# tsunami.net
KiCad netlist of a schematic drawn in EAGLE
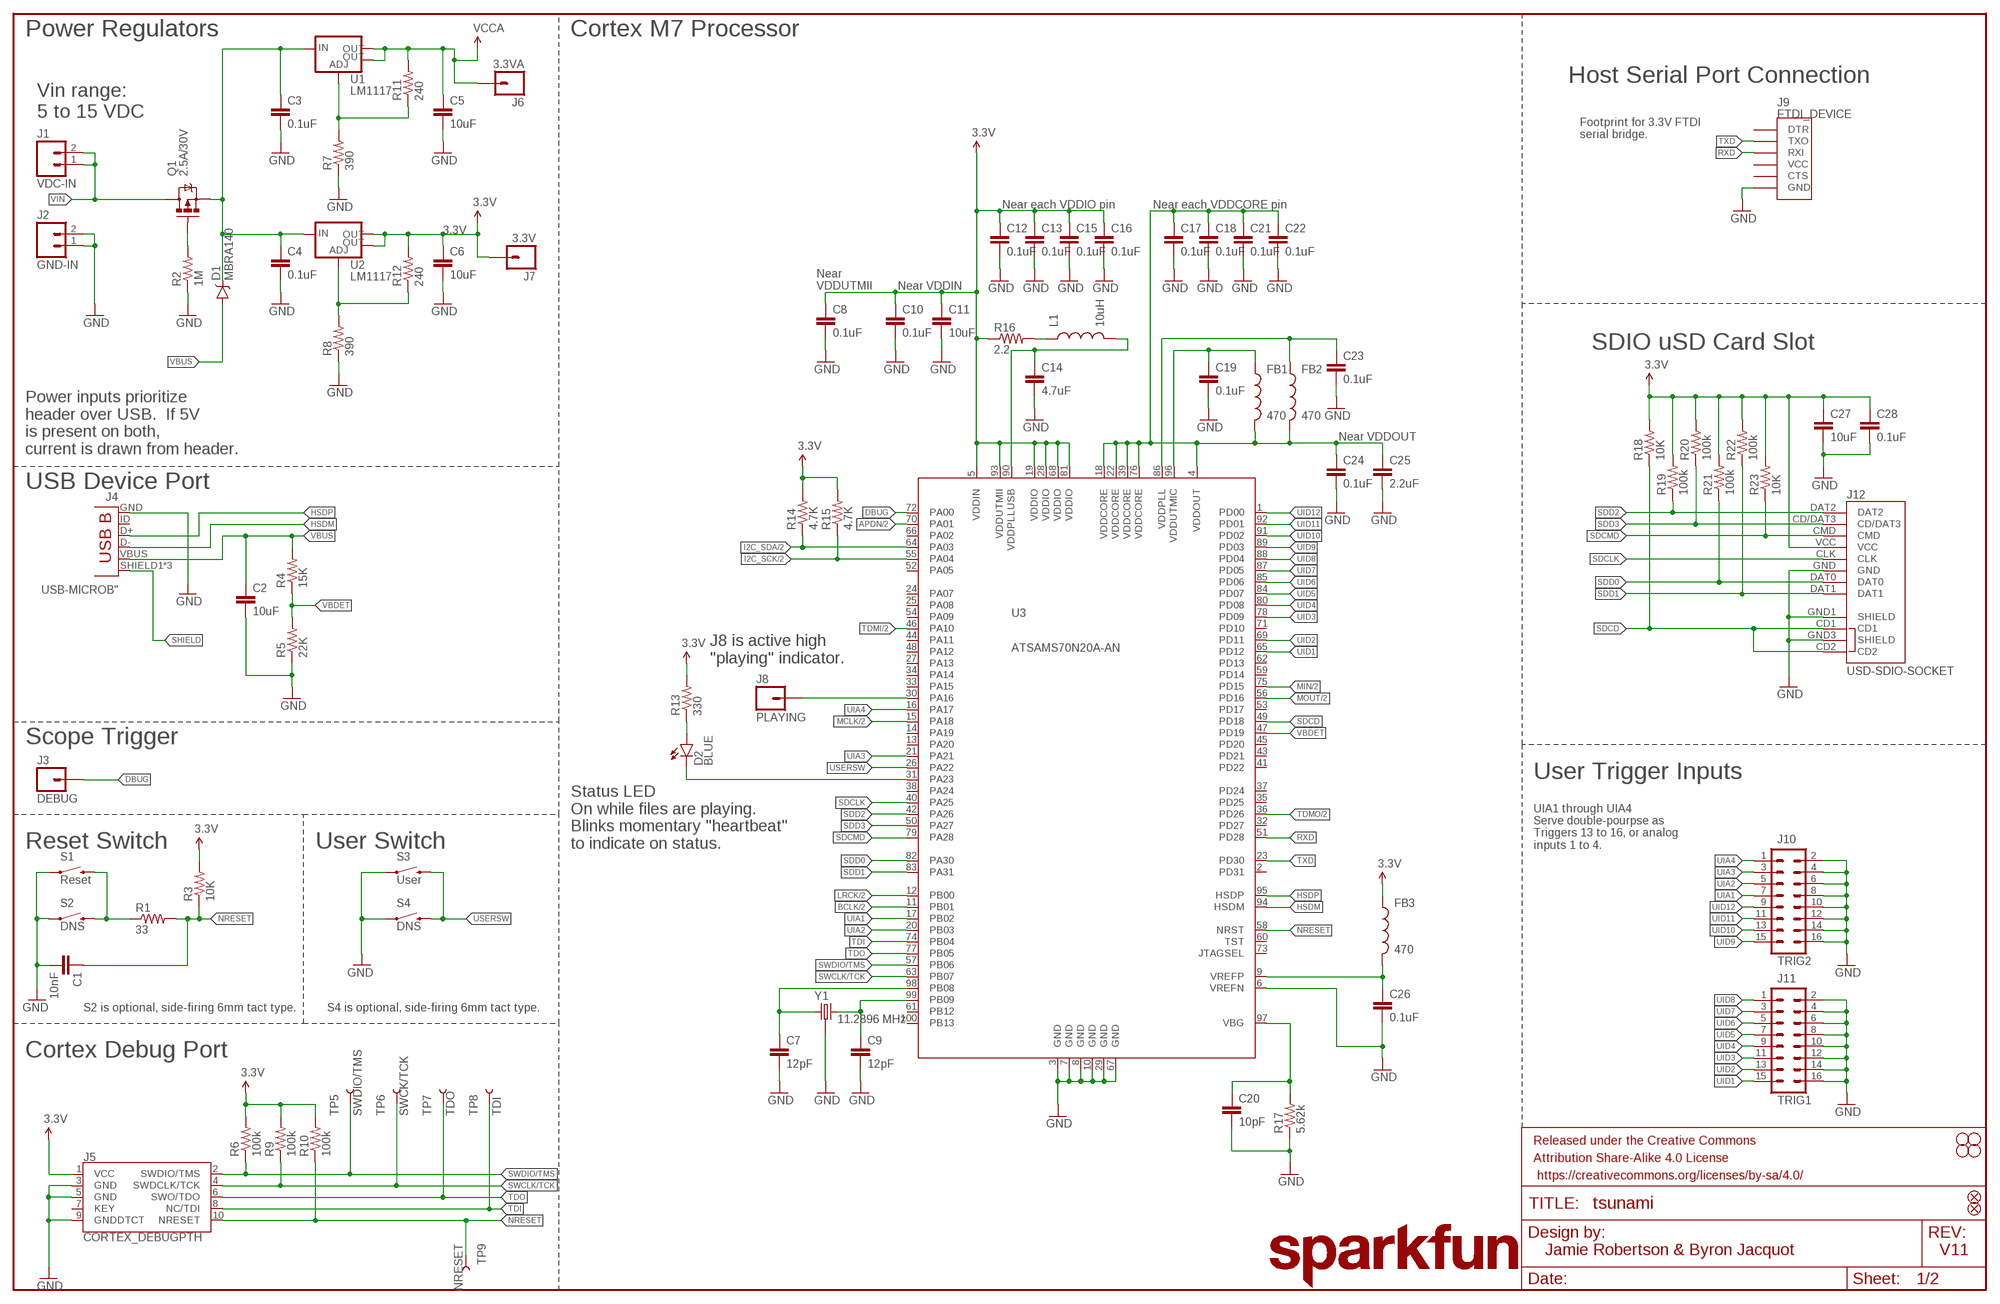
[diagram p0: schematic, sheet 1]
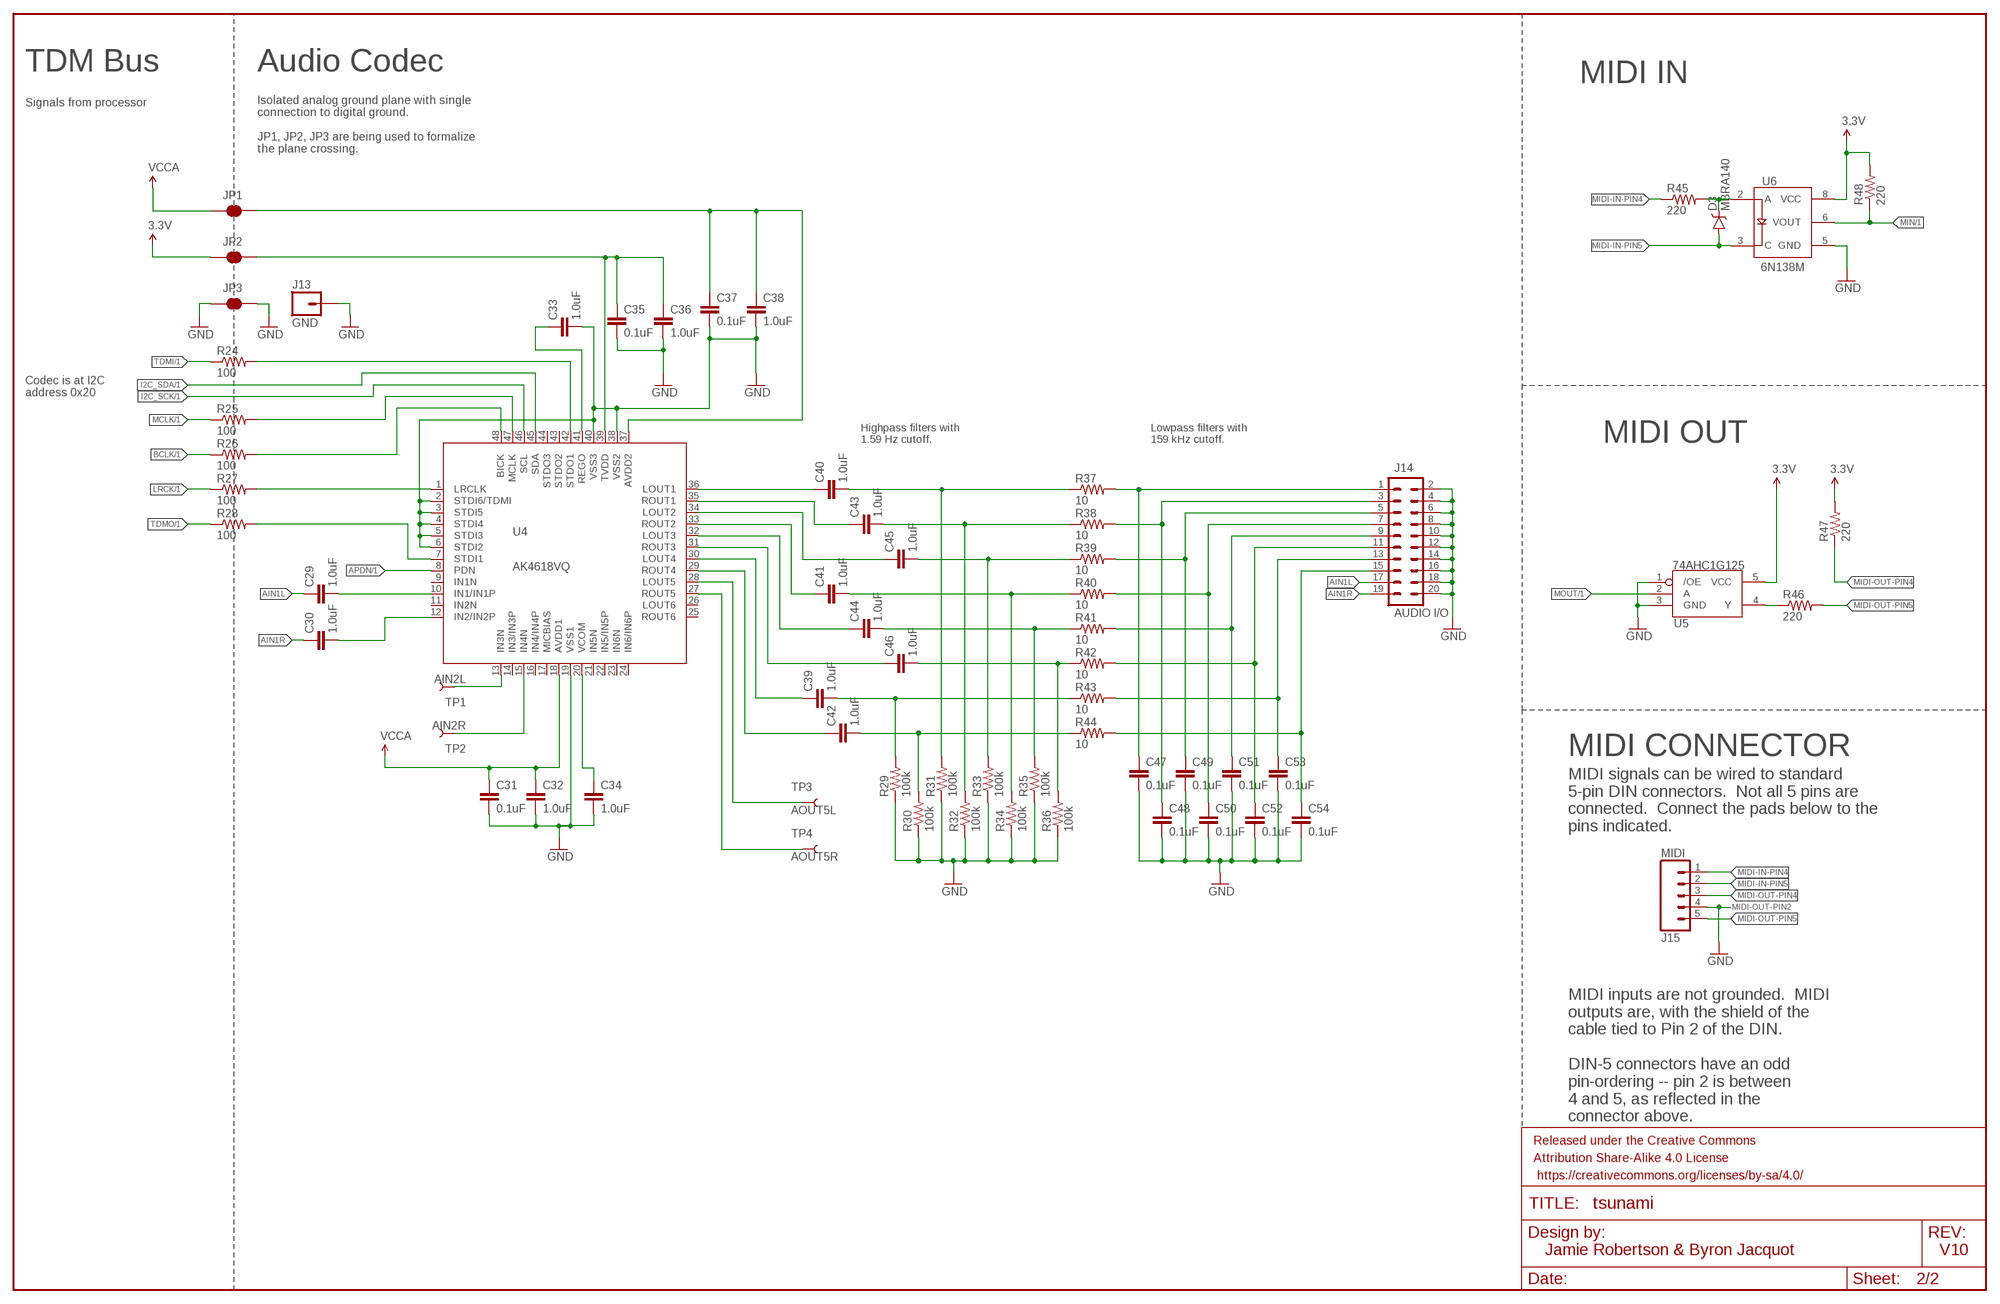
[diagram p1: schematic, sheet 2]

(export (version "E")
  (design (tool "Eeschema 10.0.6"))
  (components
    (comp (ref "C1")
      (value "10nF")
      (footprint "eagle-import:0603-CAP")
      (libsource (lib "eagle-import") (part "10NF/10000PF-50V-10%(0603)"))
    )
    (comp (ref "C2")
      (value "10uF")
      (footprint "eagle-import:0603-CAP")
      (libsource (lib "eagle-import") (part "10UF-6.3V-20%(0603)"))
    )
    (comp (ref "C3")
      (value "0.1uF")
      (footprint "eagle-import:0603-CAP")
      (libsource (lib "eagle-import") (part "0.1UF-25V(+80/-20%)(0603)"))
    )
    (comp (ref "C4")
      (value "0.1uF")
      (footprint "eagle-import:0603-CAP")
      (libsource (lib "eagle-import") (part "0.1UF-25V(+80/-20%)(0603)"))
    )
    (comp (ref "C5")
      (value "10uF")
      (footprint "eagle-import:0603-CAP")
      (libsource (lib "eagle-import") (part "10UF-6.3V-20%(0603)"))
    )
    (comp (ref "C6")
      (value "10uF")
      (footprint "eagle-import:0603-CAP")
      (libsource (lib "eagle-import") (part "10UF-6.3V-20%(0603)"))
    )
    (comp (ref "C7")
      (value "12pF")
      (footprint "eagle-import:0603-CAP")
      (libsource (lib "eagle-import") (part "12PF-50V-5%(0603)"))
    )
    (comp (ref "C8")
      (value "0.1uF")
      (footprint "eagle-import:0603-CAP")
      (libsource (lib "eagle-import") (part "0.1UF-25V(+80/-20%)(0603)"))
    )
    (comp (ref "C9")
      (value "12pF")
      (footprint "eagle-import:0603-CAP")
      (libsource (lib "eagle-import") (part "12PF-50V-5%(0603)"))
    )
    (comp (ref "C10")
      (value "0.1uF")
      (footprint "eagle-import:0603-CAP")
      (libsource (lib "eagle-import") (part "0.1UF-25V(+80/-20%)(0603)"))
    )
    (comp (ref "C11")
      (value "10uF")
      (footprint "eagle-import:0603-CAP")
      (libsource (lib "eagle-import") (part "10UF-6.3V-20%(0603)"))
    )
    (comp (ref "C12")
      (value "0.1uF")
      (footprint "eagle-import:0603-CAP")
      (libsource (lib "eagle-import") (part "0.1UF-25V(+80/-20%)(0603)"))
    )
    (comp (ref "C13")
      (value "0.1uF")
      (footprint "eagle-import:0603-CAP")
      (libsource (lib "eagle-import") (part "0.1UF-25V(+80/-20%)(0603)"))
    )
    (comp (ref "C14")
      (value "4.7uF")
      (footprint "eagle-import:0603-CAP")
      (libsource (lib "eagle-import") (part "4.7UF-6.3V-10%(0603)0603"))
    )
    (comp (ref "C15")
      (value "0.1uF")
      (footprint "eagle-import:0603-CAP")
      (libsource (lib "eagle-import") (part "0.1UF-25V(+80/-20%)(0603)"))
    )
    (comp (ref "C16")
      (value "0.1uF")
      (footprint "eagle-import:0603-CAP")
      (libsource (lib "eagle-import") (part "0.1UF-25V(+80/-20%)(0603)"))
    )
    (comp (ref "C17")
      (value "0.1uF")
      (footprint "eagle-import:0603-CAP")
      (libsource (lib "eagle-import") (part "0.1UF-25V(+80/-20%)(0603)"))
    )
    (comp (ref "C18")
      (value "0.1uF")
      (footprint "eagle-import:0603-CAP")
      (libsource (lib "eagle-import") (part "0.1UF-25V(+80/-20%)(0603)"))
    )
    (comp (ref "C19")
      (value "0.1uF")
      (footprint "eagle-import:0603-CAP")
      (libsource (lib "eagle-import") (part "0.1UF-25V(+80/-20%)(0603)"))
    )
    (comp (ref "C20")
      (value "10pF")
      (footprint "eagle-import:0603-CAP")
      (libsource (lib "eagle-import") (part "10PF-50V-5%(0603)"))
    )
    (comp (ref "C21")
      (value "0.1uF")
      (footprint "eagle-import:0603-CAP")
      (libsource (lib "eagle-import") (part "0.1UF-25V(+80/-20%)(0603)"))
    )
    (comp (ref "C22")
      (value "0.1uF")
      (footprint "eagle-import:0603-CAP")
      (libsource (lib "eagle-import") (part "0.1UF-25V(+80/-20%)(0603)"))
    )
    (comp (ref "C23")
      (value "0.1uF")
      (footprint "eagle-import:0603-CAP")
      (libsource (lib "eagle-import") (part "0.1UF-25V(+80/-20%)(0603)"))
    )
    (comp (ref "C24")
      (value "0.1uF")
      (footprint "eagle-import:0603-CAP")
      (libsource (lib "eagle-import") (part "0.1UF-25V(+80/-20%)(0603)"))
    )
    (comp (ref "C25")
      (value "2.2uF")
      (footprint "eagle-import:0603-CAP")
      (libsource (lib "eagle-import") (part "2.2UF-10V-20%(0603)"))
    )
    (comp (ref "C26")
      (value "0.1uF")
      (footprint "eagle-import:0603-CAP")
      (libsource (lib "eagle-import") (part "0.1UF-25V(+80/-20%)(0603)"))
    )
    (comp (ref "C27")
      (value "10uF")
      (footprint "eagle-import:0603-CAP")
      (libsource (lib "eagle-import") (part "10UF-6.3V-20%(0603)"))
    )
    (comp (ref "C28")
      (value "0.1uF")
      (footprint "eagle-import:0603-CAP")
      (libsource (lib "eagle-import") (part "0.1UF-25V(+80/-20%)(0603)"))
    )
    (comp (ref "D1")
      (value "MBRA140")
      (footprint "eagle-import:SMA-DIODE")
      (libsource (lib "eagle-import") (part "DIODE-SCHOTTKY-MBRA140"))
    )
    (comp (ref "D2")
      (value "BLUE")
      (footprint "eagle-import:LED-0603")
      (libsource (lib "eagle-import") (part "LED-BLUE0603"))
    )
    (comp (ref "FB1")
      (value "470")
      (footprint "eagle-import:0603")
      (libsource (lib "eagle-import") (part "INDUCTOR0603"))
    )
    (comp (ref "FB2")
      (value "470")
      (footprint "eagle-import:0603")
      (libsource (lib "eagle-import") (part "INDUCTOR0603"))
    )
    (comp (ref "FB3")
      (value "470")
      (footprint "eagle-import:0603")
      (libsource (lib "eagle-import") (part "INDUCTOR0603"))
    )
    (comp (ref "FD1")
      (value "FIDUCIALUFIDUCIAL")
      (footprint "eagle-import:MICRO-FIDUCIAL")
      (libsource (lib "eagle-import") (part "FIDUCIALUFIDUCIAL"))
    )
    (comp (ref "FD2")
      (value "FIDUCIALUFIDUCIAL")
      (footprint "eagle-import:MICRO-FIDUCIAL")
      (libsource (lib "eagle-import") (part "FIDUCIALUFIDUCIAL"))
    )
    (comp (ref "FRAME1")
      (value "FRAME-LEDGER")
      (footprint "eagle-import:CREATIVE_COMMONS")
      (libsource (lib "eagle-import") (part "FRAME-LEDGER"))
    )
    (comp (ref "H1")
      (value "STAND-OFF")
      (footprint "eagle-import:STAND-OFF")
      (libsource (lib "eagle-import") (part "STAND-OFF"))
    )
    (comp (ref "H2")
      (value "STAND-OFF")
      (footprint "eagle-import:STAND-OFF")
      (libsource (lib "eagle-import") (part "STAND-OFF"))
    )
    (comp (ref "H3")
      (value "STAND-OFF")
      (footprint "eagle-import:STAND-OFF")
      (libsource (lib "eagle-import") (part "STAND-OFF"))
    )
    (comp (ref "H4")
      (value "STAND-OFF")
      (footprint "eagle-import:STAND-OFF")
      (libsource (lib "eagle-import") (part "STAND-OFF"))
    )
    (comp (ref "J1")
      (value "VDC-IN")
      (footprint "eagle-import:1X02")
      (libsource (lib "eagle-import") (part "M02PTH"))
    )
    (comp (ref "J2")
      (value "GND-IN")
      (footprint "eagle-import:1X02")
      (libsource (lib "eagle-import") (part "M02PTH"))
    )
    (comp (ref "J3")
      (value "DEBUG")
      (footprint "eagle-import:1X01_NO_SILK")
      (libsource (lib "eagle-import") (part "M01PTH_NO_SILK_YES_STOP"))
    )
    (comp (ref "J4")
      (value "USB-MICROB\"")
      (footprint "eagle-import:USB-B-MICRO-SMD_V03")
      (libsource (lib "eagle-import") (part "USB-MICROB{dblquote}"))
    )
    (comp (ref "J5")
      (value "CORTEX_DEBUGPTH")
      (footprint "eagle-import:2X5-PTH-1.27MM")
      (libsource (lib "eagle-import") (part "CORTEX_DEBUGPTH"))
    )
    (comp (ref "J6")
      (value "3.3VA")
      (footprint "eagle-import:1X01_NO_SILK")
      (libsource (lib "eagle-import") (part "M01PTH_NO_SILK_YES_STOP"))
    )
    (comp (ref "J7")
      (value "3.3V")
      (footprint "eagle-import:1X01_NO_SILK")
      (libsource (lib "eagle-import") (part "M01PTH_NO_SILK_YES_STOP"))
    )
    (comp (ref "J8")
      (value "PLAYING")
      (footprint "eagle-import:1X01_NO_SILK")
      (libsource (lib "eagle-import") (part "M01PTH_NO_SILK_YES_STOP"))
    )
    (comp (ref "J9")
      (value "FTDI_DEVICE")
      (footprint "eagle-import:FTDI_DEVICE_SIDE")
      (libsource (lib "eagle-import") (part "FTDI_DEVICE"))
    )
    (comp (ref "J10")
      (value "TRIG2")
      (footprint "eagle-import:2X8")
      (libsource (lib "eagle-import") (part "M08X2"))
    )
    (comp (ref "J11")
      (value "TRIG1")
      (footprint "eagle-import:2X8")
      (libsource (lib "eagle-import") (part "M08X2"))
    )
    (comp (ref "J12")
      (value "USD-SDIO-SOCKET")
      (footprint "eagle-import:MICRO-SD-SOCKET-SDIO")
      (libsource (lib "eagle-import") (part "USD-SDIO-SOCKET"))
    )
    (comp (ref "L1")
      (value "10uH")
      (footprint "eagle-import:0805")
      (libsource (lib "eagle-import") (part "INDUCTOR0805"))
    )
    (comp (ref "LOGO1")
      (value "SFE_LOGO_NAME.2_INCH")
      (footprint "eagle-import:SFE_LOGO_NAME_.2")
      (libsource (lib "eagle-import") (part "SFE_LOGO_NAME.2_INCH"))
    )
    (comp (ref "Q1")
      (value "2.5A/30V")
      (footprint "eagle-import:SOT23-3")
      (libsource (lib "eagle-import") (part "MOSFET-PCHANNELDMG2307L"))
    )
    (comp (ref "R1")
      (value "33")
      (footprint "eagle-import:0603-RES")
      (libsource (lib "eagle-import") (part "33OHM1/10W1%(0603)"))
    )
    (comp (ref "R2")
      (value "1M")
      (footprint "eagle-import:0603-RES")
      (libsource (lib "eagle-import") (part "1MOHM-1/10W-1%(0603)"))
    )
    (comp (ref "R3")
      (value "10K")
      (footprint "eagle-import:0603-RES")
      (libsource (lib "eagle-import") (part "10KOHM-1/10W-1%(0603)0603"))
    )
    (comp (ref "R4")
      (value "15K")
      (footprint "eagle-import:0603-RES")
      (libsource (lib "eagle-import") (part "15KOHM1/10W1%(0603)0603"))
    )
    (comp (ref "R5")
      (value "22K")
      (footprint "eagle-import:0603-RES")
      (libsource (lib "eagle-import") (part "22KOHM1/10W1%(0603)"))
    )
    (comp (ref "R6")
      (value "100k")
      (footprint "eagle-import:0603-RES")
      (libsource (lib "eagle-import") (part "100KOHM-1/10W-1%(0603)"))
    )
    (comp (ref "R7")
      (value "390")
      (footprint "eagle-import:0603-RES")
      (libsource (lib "eagle-import") (part "390OHM1/10W1%(0603)"))
    )
    (comp (ref "R8")
      (value "390")
      (footprint "eagle-import:0603-RES")
      (libsource (lib "eagle-import") (part "390OHM1/10W1%(0603)"))
    )
    (comp (ref "R9")
      (value "100k")
      (footprint "eagle-import:0603-RES")
      (libsource (lib "eagle-import") (part "100KOHM-1/10W-1%(0603)"))
    )
    (comp (ref "R10")
      (value "100k")
      (footprint "eagle-import:0603-RES")
      (libsource (lib "eagle-import") (part "100KOHM-1/10W-1%(0603)"))
    )
    (comp (ref "R11")
      (value "240")
      (footprint "eagle-import:0603-RES")
      (libsource (lib "eagle-import") (part "240OHM1/10W1%(0603)"))
    )
    (comp (ref "R12")
      (value "240")
      (footprint "eagle-import:0603-RES")
      (libsource (lib "eagle-import") (part "240OHM1/10W1%(0603)"))
    )
    (comp (ref "R13")
      (value "330")
      (footprint "eagle-import:0603-RES")
      (libsource (lib "eagle-import") (part "330OHM1/10W1%(0603)"))
    )
    (comp (ref "R14")
      (value "4.7K")
      (footprint "eagle-import:0603-RES")
      (libsource (lib "eagle-import") (part "4.7KOHM-1/10W-1%(0603)"))
    )
    (comp (ref "R15")
      (value "4.7K")
      (footprint "eagle-import:0603-RES")
      (libsource (lib "eagle-import") (part "4.7KOHM-1/10W-1%(0603)"))
    )
    (comp (ref "R16")
      (value "2.2")
      (footprint "eagle-import:0603-RES")
      (libsource (lib "eagle-import") (part "2.2OHM-1/10W-5%(0603)"))
    )
    (comp (ref "R17")
      (value "5.62k")
      (footprint "eagle-import:0603-RES")
      (libsource (lib "eagle-import") (part "5.62KOHM1/10W1%(0603)"))
    )
    (comp (ref "R18")
      (value "10K")
      (footprint "eagle-import:0603-RES")
      (libsource (lib "eagle-import") (part "10KOHM-1/10W-1%(0603)0603"))
    )
    (comp (ref "R19")
      (value "100k")
      (footprint "eagle-import:0603-RES")
      (libsource (lib "eagle-import") (part "100KOHM-1/10W-1%(0603)"))
    )
    (comp (ref "R20")
      (value "100k")
      (footprint "eagle-import:0603-RES")
      (libsource (lib "eagle-import") (part "100KOHM-1/10W-1%(0603)"))
    )
    (comp (ref "R21")
      (value "100k")
      (footprint "eagle-import:0603-RES")
      (libsource (lib "eagle-import") (part "100KOHM-1/10W-1%(0603)"))
    )
    (comp (ref "R22")
      (value "100k")
      (footprint "eagle-import:0603-RES")
      (libsource (lib "eagle-import") (part "100KOHM-1/10W-1%(0603)"))
    )
    (comp (ref "R23")
      (value "10K")
      (footprint "eagle-import:0603-RES")
      (libsource (lib "eagle-import") (part "10KOHM-1/10W-1%(0603)0603"))
    )
    (comp (ref "S1")
      (value "Reset")
      (footprint "eagle-import:TACTILE-SWITCH-SMD")
      (libsource (lib "eagle-import") (part "SWITCH-MOMENTARY-2SMD"))
    )
    (comp (ref "S2")
      (value "DNS")
      (footprint "eagle-import:TACTILE-PTH-SIDEEZ")
      (libsource (lib "eagle-import") (part "SWITCH-MOMENTARY-2SIDE_EZ"))
    )
    (comp (ref "S3")
      (value "User")
      (footprint "eagle-import:TACTILE-SWITCH-SMD")
      (libsource (lib "eagle-import") (part "SWITCH-MOMENTARY-2SMD"))
    )
    (comp (ref "S4")
      (value "DNS")
      (footprint "eagle-import:TACTILE-PTH-SIDEEZ")
      (libsource (lib "eagle-import") (part "SWITCH-MOMENTARY-2SIDE_EZ"))
    )
    (comp (ref "TP5")
      (value "SWDIO/TMS")
      (footprint "eagle-import:TP_15TH")
      (libsource (lib "eagle-import") (part "TEST-POINTTP_15TH_THRU"))
    )
    (comp (ref "TP6")
      (value "SWCK/TCK")
      (footprint "eagle-import:TP_15TH")
      (libsource (lib "eagle-import") (part "TEST-POINTTP_15TH_THRU"))
    )
    (comp (ref "TP7")
      (value "TDO")
      (footprint "eagle-import:TP_15TH")
      (libsource (lib "eagle-import") (part "TEST-POINTTP_15TH_THRU"))
    )
    (comp (ref "TP8")
      (value "TDI")
      (footprint "eagle-import:TP_15TH")
      (libsource (lib "eagle-import") (part "TEST-POINTTP_15TH_THRU"))
    )
    (comp (ref "TP9")
      (value "NRESET")
      (footprint "eagle-import:TP_15TH")
      (libsource (lib "eagle-import") (part "TEST-POINTTP_15TH_THRU"))
    )
    (comp (ref "U1")
      (value "LM1117")
      (footprint "eagle-import:SOT223")
      (libsource (lib "eagle-import") (part "V_REG_LM1117SOT223"))
    )
    (comp (ref "U2")
      (value "LM1117")
      (footprint "eagle-import:SOT223")
      (libsource (lib "eagle-import") (part "V_REG_LM1117SOT223"))
    )
    (comp (ref "U3")
      (value "ATSAMS70N20A-AN")
      (footprint "eagle-import:LQFP100")
      (libsource (lib "eagle-import") (part "ATSAMS70NXXA-AN"))
    )
    (comp (ref "Y1")
      (value "11.2896 MHz")
      (footprint "eagle-import:CRYSTAL-OSC-SMD-5X3")
      (fields
        (field (name "DKPART") "887-2353-1-ND")
        (field (name "MFR") "txc")
        (field (name "MFRPART") "7B-11.2896MAAE-T")
      )
      (libsource (lib "eagle-import") (part "CRYSTAL-11.2896"))
    )
    (comp (ref "C29")
      (value "1.0uF")
      (footprint "eagle-import:0603-CAP")
      (libsource (lib "eagle-import") (part "1.0UF-16V-10%(0603)"))
    )
    (comp (ref "C30")
      (value "1.0uF")
      (footprint "eagle-import:0603-CAP")
      (libsource (lib "eagle-import") (part "1.0UF-16V-10%(0603)"))
    )
    (comp (ref "C31")
      (value "0.1uF")
      (footprint "eagle-import:0603-CAP")
      (libsource (lib "eagle-import") (part "0.1UF-25V(+80/-20%)(0603)"))
    )
    (comp (ref "C32")
      (value "1.0uF")
      (footprint "eagle-import:0603-CAP")
      (libsource (lib "eagle-import") (part "1.0UF-16V-10%(0603)"))
    )
    (comp (ref "C33")
      (value "1.0uF")
      (footprint "eagle-import:0603-CAP")
      (libsource (lib "eagle-import") (part "1.0UF-16V-10%(0603)"))
    )
    (comp (ref "C34")
      (value "1.0uF")
      (footprint "eagle-import:0603-CAP")
      (libsource (lib "eagle-import") (part "1.0UF-16V-10%(0603)"))
    )
    (comp (ref "C35")
      (value "0.1uF")
      (footprint "eagle-import:0603-CAP")
      (libsource (lib "eagle-import") (part "0.1UF-25V(+80/-20%)(0603)"))
    )
    (comp (ref "C36")
      (value "1.0uF")
      (footprint "eagle-import:0603-CAP")
      (libsource (lib "eagle-import") (part "1.0UF-16V-10%(0603)"))
    )
    (comp (ref "C37")
      (value "0.1uF")
      (footprint "eagle-import:0603-CAP")
      (libsource (lib "eagle-import") (part "0.1UF-25V(+80/-20%)(0603)"))
    )
    (comp (ref "C38")
      (value "1.0uF")
      (footprint "eagle-import:0603-CAP")
      (libsource (lib "eagle-import") (part "1.0UF-16V-10%(0603)"))
    )
    (comp (ref "C39")
      (value "1.0uF")
      (footprint "eagle-import:0603-CAP")
      (libsource (lib "eagle-import") (part "1.0UF-16V-10%(0603)"))
    )
    (comp (ref "C40")
      (value "1.0uF")
      (footprint "eagle-import:0603-CAP")
      (libsource (lib "eagle-import") (part "1.0UF-16V-10%(0603)"))
    )
    (comp (ref "C41")
      (value "1.0uF")
      (footprint "eagle-import:0603-CAP")
      (libsource (lib "eagle-import") (part "1.0UF-16V-10%(0603)"))
    )
    (comp (ref "C42")
      (value "1.0uF")
      (footprint "eagle-import:0603-CAP")
      (libsource (lib "eagle-import") (part "1.0UF-16V-10%(0603)"))
    )
    (comp (ref "C43")
      (value "1.0uF")
      (footprint "eagle-import:0603-CAP")
      (libsource (lib "eagle-import") (part "1.0UF-16V-10%(0603)"))
    )
    (comp (ref "C44")
      (value "1.0uF")
      (footprint "eagle-import:0603-CAP")
      (libsource (lib "eagle-import") (part "1.0UF-16V-10%(0603)"))
    )
    (comp (ref "C45")
      (value "1.0uF")
      (footprint "eagle-import:0603-CAP")
      (libsource (lib "eagle-import") (part "1.0UF-16V-10%(0603)"))
    )
    (comp (ref "C46")
      (value "1.0uF")
      (footprint "eagle-import:0603-CAP")
      (libsource (lib "eagle-import") (part "1.0UF-16V-10%(0603)"))
    )
    (comp (ref "C47")
      (value "0.1uF")
      (footprint "eagle-import:0603-CAP")
      (libsource (lib "eagle-import") (part "0.1UF-25V-5%(0603)"))
    )
    (comp (ref "C48")
      (value "0.1uF")
      (footprint "eagle-import:0603-CAP")
      (libsource (lib "eagle-import") (part "0.1UF-25V-5%(0603)"))
    )
    (comp (ref "C49")
      (value "0.1uF")
      (footprint "eagle-import:0603-CAP")
      (libsource (lib "eagle-import") (part "0.1UF-25V-5%(0603)"))
    )
    (comp (ref "C50")
      (value "0.1uF")
      (footprint "eagle-import:0603-CAP")
      (libsource (lib "eagle-import") (part "0.1UF-25V-5%(0603)"))
    )
    (comp (ref "C51")
      (value "0.1uF")
      (footprint "eagle-import:0603-CAP")
      (libsource (lib "eagle-import") (part "0.1UF-25V-5%(0603)"))
    )
    (comp (ref "C52")
      (value "0.1uF")
      (footprint "eagle-import:0603-CAP")
      (libsource (lib "eagle-import") (part "0.1UF-25V-5%(0603)"))
    )
    (comp (ref "C53")
      (value "0.1uF")
      (footprint "eagle-import:0603-CAP")
      (libsource (lib "eagle-import") (part "0.1UF-25V-5%(0603)"))
    )
    (comp (ref "C54")
      (value "0.1uF")
      (footprint "eagle-import:0603-CAP")
      (libsource (lib "eagle-import") (part "0.1UF-25V-5%(0603)"))
    )
    (comp (ref "D3")
      (value "MBRA140")
      (footprint "eagle-import:SMA-DIODE")
      (libsource (lib "eagle-import") (part "MBRA140"))
    )
    (comp (ref "FRAME2")
      (value "FRAME-LEDGER")
      (footprint "eagle-import:CREATIVE_COMMONS")
      (libsource (lib "eagle-import") (part "FRAME-LEDGER"))
    )
    (comp (ref "J13")
      (value "GND")
      (footprint "eagle-import:1X01_NO_SILK")
      (libsource (lib "eagle-import") (part "M01PTH_NO_SILK_YES_STOP"))
    )
    (comp (ref "J14")
      (value "AUDIO I/O")
      (footprint "eagle-import:2X10")
      (libsource (lib "eagle-import") (part "M10X2"))
    )
    (comp (ref "J15")
      (value "MIDI")
      (footprint "eagle-import:1X05_NO_SILK")
      (libsource (lib "eagle-import") (part "M05NO_SILK"))
    )
    (comp (ref "JP1")
      (value "JUMPER-PAD-2-NC_BY_TRACENO_SILK")
      (footprint "eagle-import:PAD-JUMPER-2-NC_BY_TRACE_NO_SILK")
      (libsource (lib "eagle-import") (part "JUMPER-PAD-2-NC_BY_TRACENO_SILK"))
    )
    (comp (ref "JP2")
      (value "JUMPER-PAD-2-NC_BY_TRACENO_SILK")
      (footprint "eagle-import:PAD-JUMPER-2-NC_BY_TRACE_NO_SILK")
      (libsource (lib "eagle-import") (part "JUMPER-PAD-2-NC_BY_TRACENO_SILK"))
    )
    (comp (ref "JP3")
      (value "JUMPER-PAD-2-NC_BY_TRACENO_SILK")
      (footprint "eagle-import:PAD-JUMPER-2-NC_BY_TRACE_NO_SILK")
      (libsource (lib "eagle-import") (part "JUMPER-PAD-2-NC_BY_TRACENO_SILK"))
    )
    (comp (ref "R24")
      (value "100")
      (footprint "eagle-import:0603-RES")
      (libsource (lib "eagle-import") (part "100OHM-1/10W-1%(0603)"))
    )
    (comp (ref "R25")
      (value "100")
      (footprint "eagle-import:0603-RES")
      (libsource (lib "eagle-import") (part "100OHM-1/10W-1%(0603)"))
    )
    (comp (ref "R26")
      (value "100")
      (footprint "eagle-import:0603-RES")
      (libsource (lib "eagle-import") (part "100OHM-1/10W-1%(0603)"))
    )
    (comp (ref "R27")
      (value "100")
      (footprint "eagle-import:0603-RES")
      (libsource (lib "eagle-import") (part "100OHM-1/10W-1%(0603)"))
    )
    (comp (ref "R28")
      (value "100")
      (footprint "eagle-import:0603-RES")
      (libsource (lib "eagle-import") (part "100OHM-1/10W-1%(0603)"))
    )
    (comp (ref "R29")
      (value "100k")
      (footprint "eagle-import:0603-RES")
      (libsource (lib "eagle-import") (part "100KOHM-1/10W-1%(0603)"))
    )
    (comp (ref "R30")
      (value "100k")
      (footprint "eagle-import:0603-RES")
      (libsource (lib "eagle-import") (part "100KOHM-1/10W-1%(0603)"))
    )
    (comp (ref "R31")
      (value "100k")
      (footprint "eagle-import:0603-RES")
      (libsource (lib "eagle-import") (part "100KOHM-1/10W-1%(0603)"))
    )
    (comp (ref "R32")
      (value "100k")
      (footprint "eagle-import:0603-RES")
      (libsource (lib "eagle-import") (part "100KOHM-1/10W-1%(0603)"))
    )
    (comp (ref "R33")
      (value "100k")
      (footprint "eagle-import:0603-RES")
      (libsource (lib "eagle-import") (part "100KOHM-1/10W-1%(0603)"))
    )
    (comp (ref "R34")
      (value "100k")
      (footprint "eagle-import:0603-RES")
      (libsource (lib "eagle-import") (part "100KOHM-1/10W-1%(0603)"))
    )
    (comp (ref "R35")
      (value "100k")
      (footprint "eagle-import:0603-RES")
      (libsource (lib "eagle-import") (part "100KOHM-1/10W-1%(0603)"))
    )
    (comp (ref "R36")
      (value "100k")
      (footprint "eagle-import:0603-RES")
      (libsource (lib "eagle-import") (part "100KOHM-1/10W-1%(0603)"))
    )
    (comp (ref "R37")
      (value "10")
      (footprint "eagle-import:0603-RES")
      (libsource (lib "eagle-import") (part "10OHM-1/10W-1%(0603)SMD"))
    )
    (comp (ref "R38")
      (value "10")
      (footprint "eagle-import:0603-RES")
      (libsource (lib "eagle-import") (part "10OHM-1/10W-1%(0603)SMD"))
    )
    (comp (ref "R39")
      (value "10")
      (footprint "eagle-import:0603-RES")
      (libsource (lib "eagle-import") (part "10OHM-1/10W-1%(0603)SMD"))
    )
    (comp (ref "R40")
      (value "10")
      (footprint "eagle-import:0603-RES")
      (libsource (lib "eagle-import") (part "10OHM-1/10W-1%(0603)SMD"))
    )
    (comp (ref "R41")
      (value "10")
      (footprint "eagle-import:0603-RES")
      (libsource (lib "eagle-import") (part "10OHM-1/10W-1%(0603)SMD"))
    )
    (comp (ref "R42")
      (value "10")
      (footprint "eagle-import:0603-RES")
      (libsource (lib "eagle-import") (part "10OHM-1/10W-1%(0603)SMD"))
    )
    (comp (ref "R43")
      (value "10")
      (footprint "eagle-import:0603-RES")
      (libsource (lib "eagle-import") (part "10OHM-1/10W-1%(0603)SMD"))
    )
    (comp (ref "R44")
      (value "10")
      (footprint "eagle-import:0603-RES")
      (libsource (lib "eagle-import") (part "10OHM-1/10W-1%(0603)SMD"))
    )
    (comp (ref "R45")
      (value "220")
      (footprint "eagle-import:0603-RES")
      (libsource (lib "eagle-import") (part "220OHM-1/10W-1%(0603)"))
    )
    (comp (ref "R46")
      (value "220")
      (footprint "eagle-import:0603-RES")
      (libsource (lib "eagle-import") (part "220OHM-1/10W-1%(0603)"))
    )
    (comp (ref "R47")
      (value "220")
      (footprint "eagle-import:0603-RES")
      (libsource (lib "eagle-import") (part "220OHM-1/10W-1%(0603)"))
    )
    (comp (ref "R48")
      (value "220")
      (footprint "eagle-import:0603-RES")
      (libsource (lib "eagle-import") (part "220OHM-1/10W-1%(0603)"))
    )
    (comp (ref "TP1")
      (value "AIN2L")
      (footprint "eagle-import:TP_15TH")
      (libsource (lib "eagle-import") (part "TEST-POINTTP_15TH_THRU"))
    )
    (comp (ref "TP2")
      (value "AIN2R")
      (footprint "eagle-import:TP_15TH")
      (libsource (lib "eagle-import") (part "TEST-POINTTP_15TH_THRU"))
    )
    (comp (ref "TP3")
      (value "AOUT5L")
      (footprint "eagle-import:TP_15TH")
      (libsource (lib "eagle-import") (part "TEST-POINTTP_15TH_THRU"))
    )
    (comp (ref "TP4")
      (value "AOUT5R")
      (footprint "eagle-import:TP_15TH")
      (libsource (lib "eagle-import") (part "TEST-POINTTP_15TH_THRU"))
    )
    (comp (ref "U4")
      (value "AK4618VQ")
      (footprint "eagle-import:LQFP-48")
      (libsource (lib "eagle-import") (part "AK4618VQSFE-PACKAGE"))
    )
    (comp (ref "U5")
      (value "74AHC1G125")
      (footprint "eagle-import:SOT23-5")
      (libsource (lib "eagle-import") (part "74AHC1G125"))
    )
    (comp (ref "U6")
      (value "6N138M")
      (footprint "eagle-import:8-SMD")
      (libsource (lib "eagle-import") (part "OPTO_DARL_6N138S"))
    )
  )
  (nets
    (net (code "1") (name "3.3V") (class "Default")
      (node (ref "C10") (pin "1") (pinfunction "1_1") (pintype "passive"))
      (node (ref "C11") (pin "1") (pinfunction "1_1") (pintype "passive"))
      (node (ref "C12") (pin "1") (pinfunction "1_1") (pintype "passive"))
      (node (ref "C13") (pin "1") (pinfunction "1_1") (pintype "passive"))
      (node (ref "C15") (pin "1") (pinfunction "1_1") (pintype "passive"))
      (node (ref "C16") (pin "1") (pinfunction "1_1") (pintype "passive"))
      (node (ref "C27") (pin "1") (pinfunction "1_1") (pintype "passive"))
      (node (ref "C28") (pin "1") (pinfunction "1_1") (pintype "passive"))
      (node (ref "C35") (pin "1") (pinfunction "1_1") (pintype "passive"))
      (node (ref "C36") (pin "1") (pinfunction "1_1") (pintype "passive"))
      (node (ref "C6") (pin "1") (pinfunction "1_1") (pintype "passive"))
      (node (ref "C8") (pin "1") (pinfunction "1_1") (pintype "passive"))
      (node (ref "FB3") (pin "1") (pinfunction "1_1") (pintype "passive"))
      (node (ref "J12") (pin "VCC") (pinfunction "VCC_VCC") (pintype "bidirectional"))
      (node (ref "J5") (pin "1") (pinfunction "VCC_1") (pintype "bidirectional"))
      (node (ref "J7") (pin "1") (pinfunction "1_1") (pintype "passive"))
      (node (ref "JP2") (pin "1") (pinfunction "1_1") (pintype "passive"))
      (node (ref "JP2") (pin "2") (pinfunction "2_2") (pintype "passive"))
      (node (ref "R10") (pin "2") (pinfunction "2_2") (pintype "passive"))
      (node (ref "R12") (pin "2") (pinfunction "2_2") (pintype "passive"))
      (node (ref "R13") (pin "2") (pinfunction "2_2") (pintype "passive"))
      (node (ref "R14") (pin "2") (pinfunction "2_2") (pintype "passive"))
      (node (ref "R15") (pin "2") (pinfunction "2_2") (pintype "passive"))
      (node (ref "R16") (pin "1") (pinfunction "1_1") (pintype "passive"))
      (node (ref "R18") (pin "2") (pinfunction "2_2") (pintype "passive"))
      (node (ref "R19") (pin "2") (pinfunction "2_2") (pintype "passive"))
      (node (ref "R20") (pin "2") (pinfunction "2_2") (pintype "passive"))
      (node (ref "R21") (pin "2") (pinfunction "2_2") (pintype "passive"))
      (node (ref "R22") (pin "2") (pinfunction "2_2") (pintype "passive"))
      (node (ref "R23") (pin "2") (pinfunction "2_2") (pintype "passive"))
      (node (ref "R3") (pin "2") (pinfunction "2_2") (pintype "passive"))
      (node (ref "R47") (pin "2") (pinfunction "2_2") (pintype "passive"))
      (node (ref "R48") (pin "2") (pinfunction "2_2") (pintype "passive"))
      (node (ref "R6") (pin "2") (pinfunction "2_2") (pintype "passive"))
      (node (ref "R9") (pin "2") (pinfunction "2_2") (pintype "passive"))
      (node (ref "U2") (pin "2") (pinfunction "OUT_2") (pintype "output"))
      (node (ref "U2") (pin "4") (pinfunction "OUT_4") (pintype "output"))
      (node (ref "U3") (pin "19") (pinfunction "VDDIO_19") (pintype "bidirectional"))
      (node (ref "U3") (pin "28") (pinfunction "VDDIO_28") (pintype "bidirectional"))
      (node (ref "U3") (pin "5") (pinfunction "VDDIN_5") (pintype "bidirectional"))
      (node (ref "U3") (pin "68") (pinfunction "VDDIO_68") (pintype "bidirectional"))
      (node (ref "U3") (pin "81") (pinfunction "VDDIO_81") (pintype "bidirectional"))
      (node (ref "U3") (pin "93") (pinfunction "VDDUTMII_93") (pintype "bidirectional"))
      (node (ref "U4") (pin "39") (pinfunction "TVDD_39") (pintype "bidirectional"))
      (node (ref "U5") (pin "5") (pinfunction "VCC_5") (pintype "bidirectional"))
      (node (ref "U6") (pin "8") (pinfunction "VCC_8") (pintype "bidirectional"))
    )
    (net (code "2") (name "AIN1L") (class "Default")
      (node (ref "C29") (pin "1") (pinfunction "1_1") (pintype "passive"))
      (node (ref "J14") (pin "17") (pinfunction "17_17") (pintype "passive"))
    )
    (net (code "3") (name "AIN1R") (class "Default")
      (node (ref "C30") (pin "1") (pinfunction "1_1") (pintype "passive"))
      (node (ref "J14") (pin "19") (pinfunction "19_19") (pintype "passive"))
    )
    (net (code "4") (name "APDN") (class "Default")
      (node (ref "U3") (pin "70") (pinfunction "PA01_70") (pintype "bidirectional"))
      (node (ref "U4") (pin "8") (pinfunction "PDN_8") (pintype "bidirectional"))
    )
    (net (code "5") (name "BCLK") (class "Default")
      (node (ref "R26") (pin "1") (pinfunction "1_1") (pintype "passive"))
      (node (ref "U3") (pin "11") (pinfunction "PB01_11") (pintype "bidirectional"))
    )
    (net (code "6") (name "DBUG") (class "Default")
      (node (ref "J3") (pin "1") (pinfunction "1_1") (pintype "passive"))
      (node (ref "U3") (pin "72") (pinfunction "PA00_72") (pintype "bidirectional"))
    )
    (net (code "7") (name "GND") (class "Default")
      (node (ref "C1") (pin "2") (pinfunction "2_2") (pintype "passive"))
      (node (ref "C10") (pin "2") (pinfunction "2_2") (pintype "passive"))
      (node (ref "C11") (pin "2") (pinfunction "2_2") (pintype "passive"))
      (node (ref "C12") (pin "2") (pinfunction "2_2") (pintype "passive"))
      (node (ref "C13") (pin "2") (pinfunction "2_2") (pintype "passive"))
      (node (ref "C14") (pin "2") (pinfunction "2_2") (pintype "passive"))
      (node (ref "C15") (pin "2") (pinfunction "2_2") (pintype "passive"))
      (node (ref "C16") (pin "2") (pinfunction "2_2") (pintype "passive"))
      (node (ref "C17") (pin "2") (pinfunction "2_2") (pintype "passive"))
      (node (ref "C18") (pin "2") (pinfunction "2_2") (pintype "passive"))
      (node (ref "C19") (pin "2") (pinfunction "2_2") (pintype "passive"))
      (node (ref "C2") (pin "2") (pinfunction "2_2") (pintype "passive"))
      (node (ref "C20") (pin "2") (pinfunction "2_2") (pintype "passive"))
      (node (ref "C21") (pin "2") (pinfunction "2_2") (pintype "passive"))
      (node (ref "C22") (pin "2") (pinfunction "2_2") (pintype "passive"))
      (node (ref "C23") (pin "2") (pinfunction "2_2") (pintype "passive"))
      (node (ref "C24") (pin "2") (pinfunction "2_2") (pintype "passive"))
      (node (ref "C25") (pin "2") (pinfunction "2_2") (pintype "passive"))
      (node (ref "C26") (pin "2") (pinfunction "2_2") (pintype "passive"))
      (node (ref "C27") (pin "2") (pinfunction "2_2") (pintype "passive"))
      (node (ref "C28") (pin "2") (pinfunction "2_2") (pintype "passive"))
      (node (ref "C3") (pin "2") (pinfunction "2_2") (pintype "passive"))
      (node (ref "C31") (pin "2") (pinfunction "2_2") (pintype "passive"))
      (node (ref "C32") (pin "2") (pinfunction "2_2") (pintype "passive"))
      (node (ref "C33") (pin "2") (pinfunction "2_2") (pintype "passive"))
      (node (ref "C34") (pin "2") (pinfunction "2_2") (pintype "passive"))
      (node (ref "C35") (pin "2") (pinfunction "2_2") (pintype "passive"))
      (node (ref "C36") (pin "2") (pinfunction "2_2") (pintype "passive"))
      (node (ref "C37") (pin "2") (pinfunction "2_2") (pintype "passive"))
      (node (ref "C38") (pin "2") (pinfunction "2_2") (pintype "passive"))
      (node (ref "C4") (pin "2") (pinfunction "2_2") (pintype "passive"))
      (node (ref "C47") (pin "2") (pinfunction "2_2") (pintype "passive"))
      (node (ref "C48") (pin "2") (pinfunction "2_2") (pintype "passive"))
      (node (ref "C49") (pin "2") (pinfunction "2_2") (pintype "passive"))
      (node (ref "C5") (pin "2") (pinfunction "2_2") (pintype "passive"))
      (node (ref "C50") (pin "2") (pinfunction "2_2") (pintype "passive"))
      (node (ref "C51") (pin "2") (pinfunction "2_2") (pintype "passive"))
      (node (ref "C52") (pin "2") (pinfunction "2_2") (pintype "passive"))
      (node (ref "C53") (pin "2") (pinfunction "2_2") (pintype "passive"))
      (node (ref "C54") (pin "2") (pinfunction "2_2") (pintype "passive"))
      (node (ref "C6") (pin "2") (pinfunction "2_2") (pintype "passive"))
      (node (ref "C7") (pin "2") (pinfunction "2_2") (pintype "passive"))
      (node (ref "C8") (pin "2") (pinfunction "2_2") (pintype "passive"))
      (node (ref "C9") (pin "2") (pinfunction "2_2") (pintype "passive"))
      (node (ref "J10") (pin "10") (pinfunction "10_10") (pintype "passive"))
      (node (ref "J10") (pin "12") (pinfunction "12_12") (pintype "passive"))
      (node (ref "J10") (pin "14") (pinfunction "14_14") (pintype "passive"))
      (node (ref "J10") (pin "16") (pinfunction "16_16") (pintype "passive"))
      (node (ref "J10") (pin "2") (pinfunction "2_2") (pintype "passive"))
      (node (ref "J10") (pin "4") (pinfunction "4_4") (pintype "passive"))
      (node (ref "J10") (pin "6") (pinfunction "6_6") (pintype "passive"))
      (node (ref "J10") (pin "8") (pinfunction "8_8") (pintype "passive"))
      (node (ref "J11") (pin "10") (pinfunction "10_10") (pintype "passive"))
      (node (ref "J11") (pin "12") (pinfunction "12_12") (pintype "passive"))
      (node (ref "J11") (pin "14") (pinfunction "14_14") (pintype "passive"))
      (node (ref "J11") (pin "16") (pinfunction "16_16") (pintype "passive"))
      (node (ref "J11") (pin "2") (pinfunction "2_2") (pintype "passive"))
      (node (ref "J11") (pin "4") (pinfunction "4_4") (pintype "passive"))
      (node (ref "J11") (pin "6") (pinfunction "6_6") (pintype "passive"))
      (node (ref "J11") (pin "8") (pinfunction "8_8") (pintype "passive"))
      (node (ref "J12") (pin "GND") (pinfunction "GND_GND") (pintype "bidirectional"))
      (node (ref "J12") (pin "GND1") (pinfunction "SHIELD_GND1") (pintype "bidirectional"))
      (node (ref "J12") (pin "GND3") (pinfunction "SHIELD_GND3") (pintype "bidirectional"))
      (node (ref "J13") (pin "1") (pinfunction "1_1") (pintype "passive"))
      (node (ref "J14") (pin "10") (pinfunction "10_10") (pintype "passive"))
      (node (ref "J14") (pin "12") (pinfunction "12_12") (pintype "passive"))
      (node (ref "J14") (pin "14") (pinfunction "14_14") (pintype "passive"))
      (node (ref "J14") (pin "16") (pinfunction "16_16") (pintype "passive"))
      (node (ref "J14") (pin "18") (pinfunction "18_18") (pintype "passive"))
      (node (ref "J14") (pin "2") (pinfunction "2_2") (pintype "passive"))
      (node (ref "J14") (pin "20") (pinfunction "20_20") (pintype "passive"))
      (node (ref "J14") (pin "4") (pinfunction "4_4") (pintype "passive"))
      (node (ref "J14") (pin "6") (pinfunction "6_6") (pintype "passive"))
      (node (ref "J14") (pin "8") (pinfunction "8_8") (pintype "passive"))
      (node (ref "J15") (pin "4") (pinfunction "4_4") (pintype "passive"))
      (node (ref "J2") (pin "1") (pinfunction "1_1") (pintype "passive"))
      (node (ref "J2") (pin "2") (pinfunction "2_2") (pintype "passive"))
      (node (ref "J4") (pin "GND") (pinfunction "GND_GND") (pintype "bidirectional"))
      (node (ref "J5") (pin "3") (pinfunction "GND_3") (pintype "bidirectional"))
      (node (ref "J5") (pin "5") (pinfunction "GND_5") (pintype "bidirectional"))
      (node (ref "J5") (pin "9") (pinfunction "GNDDTCT_9") (pintype "bidirectional"))
      (node (ref "J9") (pin "P$6") (pinfunction "GND_P$6") (pintype "bidirectional"))
      (node (ref "JP3") (pin "1") (pinfunction "1_1") (pintype "passive"))
      (node (ref "JP3") (pin "2") (pinfunction "2_2") (pintype "passive"))
      (node (ref "R17") (pin "1") (pinfunction "1_1") (pintype "passive"))
      (node (ref "R2") (pin "1") (pinfunction "1_1") (pintype "passive"))
      (node (ref "R29") (pin "1") (pinfunction "1_1") (pintype "passive"))
      (node (ref "R30") (pin "1") (pinfunction "1_1") (pintype "passive"))
      (node (ref "R31") (pin "1") (pinfunction "1_1") (pintype "passive"))
      (node (ref "R32") (pin "1") (pinfunction "1_1") (pintype "passive"))
      (node (ref "R33") (pin "1") (pinfunction "1_1") (pintype "passive"))
      (node (ref "R34") (pin "1") (pinfunction "1_1") (pintype "passive"))
      (node (ref "R35") (pin "1") (pinfunction "1_1") (pintype "passive"))
      (node (ref "R36") (pin "1") (pinfunction "1_1") (pintype "passive"))
      (node (ref "R5") (pin "1") (pinfunction "1_1") (pintype "passive"))
      (node (ref "R7") (pin "1") (pinfunction "1_1") (pintype "passive"))
      (node (ref "R8") (pin "1") (pinfunction "1_1") (pintype "passive"))
      (node (ref "S1") (pin "1") (pinfunction "1_1") (pintype "passive"))
      (node (ref "S2") (pin "1") (pinfunction "1_1") (pintype "passive"))
      (node (ref "S3") (pin "1") (pinfunction "1_1") (pintype "passive"))
      (node (ref "S4") (pin "1") (pinfunction "1_1") (pintype "passive"))
      (node (ref "U3") (pin "10") (pinfunction "GND_10") (pintype "bidirectional"))
      (node (ref "U3") (pin "29") (pinfunction "GND_29") (pintype "bidirectional"))
      (node (ref "U3") (pin "3") (pinfunction "GND_3") (pintype "bidirectional"))
      (node (ref "U3") (pin "6") (pinfunction "VREFN_6") (pintype "bidirectional"))
      (node (ref "U3") (pin "67") (pinfunction "GND_67") (pintype "bidirectional"))
      (node (ref "U3") (pin "7") (pinfunction "GND_7") (pintype "bidirectional"))
      (node (ref "U3") (pin "8") (pinfunction "GND_8") (pintype "bidirectional"))
      (node (ref "U4") (pin "19") (pinfunction "VSS1_19") (pintype "bidirectional"))
      (node (ref "U4") (pin "2") (pinfunction "STDI6/TDMI_2") (pintype "bidirectional"))
      (node (ref "U4") (pin "3") (pinfunction "STDI5_3") (pintype "bidirectional"))
      (node (ref "U4") (pin "38") (pinfunction "VSS2_38") (pintype "bidirectional"))
      (node (ref "U4") (pin "4") (pinfunction "STDI4_4") (pintype "bidirectional"))
      (node (ref "U4") (pin "40") (pinfunction "VSS3_40") (pintype "bidirectional"))
      (node (ref "U4") (pin "5") (pinfunction "STDI3_5") (pintype "bidirectional"))
      (node (ref "U4") (pin "6") (pinfunction "STDI2_6") (pintype "bidirectional"))
      (node (ref "U5") (pin "1") (pinfunction "/OE_1") (pintype "bidirectional"))
      (node (ref "U5") (pin "3") (pinfunction "GND_3") (pintype "bidirectional"))
      (node (ref "U6") (pin "5") (pinfunction "GND_5") (pintype "bidirectional"))
      (node (ref "Y1") (pin "2") (pinfunction "3_2") (pintype "passive"))
      (node (ref "Y1") (pin "4") (pinfunction "3_4") (pintype "passive"))
    )
    (net (code "8") (name "HSDM") (class "Default")
      (node (ref "J4") (pin "D-") (pinfunction "D-_D-") (pintype "bidirectional"))
      (node (ref "U3") (pin "94") (pinfunction "HSDM_94") (pintype "bidirectional"))
    )
    (net (code "9") (name "HSDP") (class "Default")
      (node (ref "J4") (pin "D+") (pinfunction "D+_D+") (pintype "bidirectional"))
      (node (ref "U3") (pin "95") (pinfunction "HSDP_95") (pintype "bidirectional"))
    )
    (net (code "10") (name "I2C_SCK") (class "Default")
      (node (ref "R15") (pin "1") (pinfunction "1_1") (pintype "passive"))
      (node (ref "U3") (pin "55") (pinfunction "PA04_55") (pintype "bidirectional"))
      (node (ref "U4") (pin "46") (pinfunction "SCL_46") (pintype "bidirectional"))
    )
    (net (code "11") (name "I2C_SDA") (class "Default")
      (node (ref "R14") (pin "1") (pinfunction "1_1") (pintype "passive"))
      (node (ref "U3") (pin "64") (pinfunction "PA03_64") (pintype "bidirectional"))
      (node (ref "U4") (pin "45") (pinfunction "SDA_45") (pintype "bidirectional"))
    )
    (net (code "12") (name "LRCK") (class "Default")
      (node (ref "R27") (pin "1") (pinfunction "1_1") (pintype "passive"))
      (node (ref "U3") (pin "12") (pinfunction "PB00_12") (pintype "bidirectional"))
    )
    (net (code "13") (name "MCLK") (class "Default")
      (node (ref "R25") (pin "1") (pinfunction "1_1") (pintype "passive"))
      (node (ref "U3") (pin "15") (pinfunction "PA18_15") (pintype "bidirectional"))
    )
    (net (code "14") (name "MIDI-IN-PIN4") (class "Default")
      (node (ref "J15") (pin "1") (pinfunction "1_1") (pintype "passive"))
      (node (ref "R45") (pin "1") (pinfunction "1_1") (pintype "passive"))
    )
    (net (code "15") (name "MIDI-IN-PIN5") (class "Default")
      (node (ref "D3") (pin "A") (pinfunction "A_A") (pintype "passive"))
      (node (ref "J15") (pin "2") (pinfunction "2_2") (pintype "passive"))
      (node (ref "U6") (pin "3") (pinfunction "C_3") (pintype "bidirectional"))
    )
    (net (code "16") (name "MIDI-OUT-PIN4") (class "Default")
      (node (ref "J15") (pin "3") (pinfunction "3_3") (pintype "passive"))
      (node (ref "R47") (pin "1") (pinfunction "1_1") (pintype "passive"))
    )
    (net (code "17") (name "MIDI-OUT-PIN5") (class "Default")
      (node (ref "J15") (pin "5") (pinfunction "5_5") (pintype "passive"))
      (node (ref "R46") (pin "2") (pinfunction "2_2") (pintype "passive"))
    )
    (net (code "18") (name "MIN") (class "Default")
      (node (ref "R48") (pin "1") (pinfunction "1_1") (pintype "passive"))
      (node (ref "U3") (pin "75") (pinfunction "PD15_75") (pintype "bidirectional"))
      (node (ref "U6") (pin "6") (pinfunction "VOUT_6") (pintype "bidirectional"))
    )
    (net (code "19") (name "MOUT") (class "Default")
      (node (ref "U3") (pin "56") (pinfunction "PD16_56") (pintype "bidirectional"))
      (node (ref "U5") (pin "2") (pinfunction "A_2") (pintype "bidirectional"))
    )
    (net (code "20") (name "NRESET") (class "Default")
      (node (ref "C1") (pin "1") (pinfunction "1_1") (pintype "passive"))
      (node (ref "J5") (pin "10") (pinfunction "NRESET_10") (pintype "bidirectional"))
      (node (ref "R1") (pin "2") (pinfunction "2_2") (pintype "passive"))
      (node (ref "R10") (pin "1") (pinfunction "1_1") (pintype "passive"))
      (node (ref "R3") (pin "1") (pinfunction "1_1") (pintype "passive"))
      (node (ref "TP9") (pin "P$1") (pinfunction "1_P$1") (pintype "bidirectional"))
      (node (ref "U3") (pin "58") (pinfunction "NRST_58") (pintype "bidirectional"))
    )
    (net (code "21") (name "Net-(C39-Pad2)") (class "Default")
      (node (ref "C39") (pin "2") (pinfunction "2_2") (pintype "passive"))
      (node (ref "R29") (pin "2") (pinfunction "2_2") (pintype "passive"))
      (node (ref "R43") (pin "1") (pinfunction "1_1") (pintype "passive"))
    )
    (net (code "22") (name "Net-(C40-Pad2)") (class "Default")
      (node (ref "C40") (pin "2") (pinfunction "2_2") (pintype "passive"))
      (node (ref "R31") (pin "2") (pinfunction "2_2") (pintype "passive"))
      (node (ref "R37") (pin "1") (pinfunction "1_1") (pintype "passive"))
    )
    (net (code "23") (name "Net-(C41-Pad2)") (class "Default")
      (node (ref "C41") (pin "2") (pinfunction "2_2") (pintype "passive"))
      (node (ref "R34") (pin "2") (pinfunction "2_2") (pintype "passive"))
      (node (ref "R40") (pin "1") (pinfunction "1_1") (pintype "passive"))
    )
    (net (code "24") (name "Net-(C42-Pad2)") (class "Default")
      (node (ref "C42") (pin "2") (pinfunction "2_2") (pintype "passive"))
      (node (ref "R30") (pin "2") (pinfunction "2_2") (pintype "passive"))
      (node (ref "R44") (pin "1") (pinfunction "1_1") (pintype "passive"))
    )
    (net (code "25") (name "Net-(C43-Pad2)") (class "Default")
      (node (ref "C43") (pin "2") (pinfunction "2_2") (pintype "passive"))
      (node (ref "R32") (pin "2") (pinfunction "2_2") (pintype "passive"))
      (node (ref "R38") (pin "1") (pinfunction "1_1") (pintype "passive"))
    )
    (net (code "26") (name "Net-(C44-Pad2)") (class "Default")
      (node (ref "C44") (pin "2") (pinfunction "2_2") (pintype "passive"))
      (node (ref "R35") (pin "2") (pinfunction "2_2") (pintype "passive"))
      (node (ref "R41") (pin "1") (pinfunction "1_1") (pintype "passive"))
    )
    (net (code "27") (name "Net-(C45-Pad2)") (class "Default")
      (node (ref "C45") (pin "2") (pinfunction "2_2") (pintype "passive"))
      (node (ref "R33") (pin "2") (pinfunction "2_2") (pintype "passive"))
      (node (ref "R39") (pin "1") (pinfunction "1_1") (pintype "passive"))
    )
    (net (code "28") (name "Net-(C46-Pad2)") (class "Default")
      (node (ref "C46") (pin "2") (pinfunction "2_2") (pintype "passive"))
      (node (ref "R36") (pin "2") (pinfunction "2_2") (pintype "passive"))
      (node (ref "R42") (pin "1") (pinfunction "1_1") (pintype "passive"))
    )
    (net (code "29") (name "Net-(C47-Pad1)") (class "Default")
      (node (ref "C47") (pin "1") (pinfunction "1_1") (pintype "passive"))
      (node (ref "J14") (pin "1") (pinfunction "1_1") (pintype "passive"))
      (node (ref "R37") (pin "2") (pinfunction "2_2") (pintype "passive"))
    )
    (net (code "30") (name "Net-(C48-Pad1)") (class "Default")
      (node (ref "C48") (pin "1") (pinfunction "1_1") (pintype "passive"))
      (node (ref "J14") (pin "3") (pinfunction "3_3") (pintype "passive"))
      (node (ref "R38") (pin "2") (pinfunction "2_2") (pintype "passive"))
    )
    (net (code "31") (name "Net-(C49-Pad1)") (class "Default")
      (node (ref "C49") (pin "1") (pinfunction "1_1") (pintype "passive"))
      (node (ref "J14") (pin "5") (pinfunction "5_5") (pintype "passive"))
      (node (ref "R39") (pin "2") (pinfunction "2_2") (pintype "passive"))
    )
    (net (code "32") (name "Net-(C50-Pad1)") (class "Default")
      (node (ref "C50") (pin "1") (pinfunction "1_1") (pintype "passive"))
      (node (ref "J14") (pin "7") (pinfunction "7_7") (pintype "passive"))
      (node (ref "R40") (pin "2") (pinfunction "2_2") (pintype "passive"))
    )
    (net (code "33") (name "Net-(C51-Pad1)") (class "Default")
      (node (ref "C51") (pin "1") (pinfunction "1_1") (pintype "passive"))
      (node (ref "J14") (pin "9") (pinfunction "9_9") (pintype "passive"))
      (node (ref "R41") (pin "2") (pinfunction "2_2") (pintype "passive"))
    )
    (net (code "34") (name "Net-(C52-Pad1)") (class "Default")
      (node (ref "C52") (pin "1") (pinfunction "1_1") (pintype "passive"))
      (node (ref "J14") (pin "11") (pinfunction "11_11") (pintype "passive"))
      (node (ref "R42") (pin "2") (pinfunction "2_2") (pintype "passive"))
    )
    (net (code "35") (name "Net-(C53-Pad1)") (class "Default")
      (node (ref "C53") (pin "1") (pinfunction "1_1") (pintype "passive"))
      (node (ref "J14") (pin "13") (pinfunction "13_13") (pintype "passive"))
      (node (ref "R43") (pin "2") (pinfunction "2_2") (pintype "passive"))
    )
    (net (code "36") (name "Net-(C54-Pad1)") (class "Default")
      (node (ref "C54") (pin "1") (pinfunction "1_1") (pintype "passive"))
      (node (ref "J14") (pin "15") (pinfunction "15_15") (pintype "passive"))
      (node (ref "R44") (pin "2") (pinfunction "2_2") (pintype "passive"))
    )
    (net (code "37") (name "Net-(D2-PadA)") (class "Default")
      (node (ref "D2") (pin "A") (pinfunction "A_A") (pintype "passive"))
      (node (ref "R13") (pin "1") (pinfunction "1_1") (pintype "passive"))
    )
    (net (code "38") (name "Net-(L1-Pad1)") (class "Default")
      (node (ref "L1") (pin "1") (pinfunction "1_1") (pintype "passive"))
      (node (ref "R16") (pin "2") (pinfunction "2_2") (pintype "passive"))
    )
    (net (code "39") (name "Net-(Q1-G)") (class "Default")
      (node (ref "Q1") (pin "1") (pinfunction "G_1") (pintype "passive"))
      (node (ref "R2") (pin "2") (pinfunction "2_2") (pintype "passive"))
    )
    (net (code "40") (name "Net-(Q1-S)") (class "Default")
      (node (ref "C3") (pin "1") (pinfunction "1_1") (pintype "passive"))
      (node (ref "C4") (pin "1") (pinfunction "1_1") (pintype "passive"))
      (node (ref "D1") (pin "C") (pinfunction "C_C") (pintype "passive"))
      (node (ref "Q1") (pin "2") (pinfunction "S_2") (pintype "passive"))
      (node (ref "U1") (pin "3") (pinfunction "IN_3") (pintype "input"))
      (node (ref "U2") (pin "3") (pinfunction "IN_3") (pintype "input"))
    )
    (net (code "41") (name "Net-(S1-2)") (class "Default")
      (node (ref "R1") (pin "1") (pinfunction "1_1") (pintype "passive"))
      (node (ref "S1") (pin "3") (pinfunction "2_3") (pintype "passive"))
      (node (ref "S2") (pin "2") (pinfunction "2_2") (pintype "passive"))
    )
    (net (code "42") (name "Net-(TP1-1)") (class "Default")
      (node (ref "TP1") (pin "P$1") (pinfunction "1_P$1") (pintype "bidirectional"))
      (node (ref "U4") (pin "13") (pinfunction "IN3N_13") (pintype "bidirectional"))
    )
    (net (code "43") (name "Net-(TP2-1)") (class "Default")
      (node (ref "TP2") (pin "P$1") (pinfunction "1_P$1") (pintype "bidirectional"))
      (node (ref "U4") (pin "15") (pinfunction "IN4N_15") (pintype "bidirectional"))
    )
    (net (code "44") (name "Net-(TP3-1)") (class "Default")
      (node (ref "TP3") (pin "P$1") (pinfunction "1_P$1") (pintype "bidirectional"))
      (node (ref "U4") (pin "28") (pinfunction "LOUT5_28") (pintype "bidirectional"))
    )
    (net (code "45") (name "Net-(TP4-1)") (class "Default")
      (node (ref "TP4") (pin "P$1") (pinfunction "1_P$1") (pintype "bidirectional"))
      (node (ref "U4") (pin "27") (pinfunction "ROUT5_27") (pintype "bidirectional"))
    )
    (net (code "46") (name "Net-(U1-ADJ)") (class "Default")
      (node (ref "R11") (pin "1") (pinfunction "1_1") (pintype "passive"))
      (node (ref "R7") (pin "2") (pinfunction "2_2") (pintype "passive"))
      (node (ref "U1") (pin "1") (pinfunction "ADJ_1") (pintype "input"))
    )
    (net (code "47") (name "Net-(U2-ADJ)") (class "Default")
      (node (ref "R12") (pin "1") (pinfunction "1_1") (pintype "passive"))
      (node (ref "R8") (pin "2") (pinfunction "2_2") (pintype "passive"))
      (node (ref "U2") (pin "1") (pinfunction "ADJ_1") (pintype "input"))
    )
    (net (code "48") (name "Net-(U3-PA16)") (class "Default")
      (node (ref "J8") (pin "1") (pinfunction "1_1") (pintype "passive"))
      (node (ref "U3") (pin "30") (pinfunction "PA16_30") (pintype "bidirectional"))
    )
    (net (code "49") (name "Net-(U3-PA23)") (class "Default")
      (node (ref "D2") (pin "C") (pinfunction "C_C") (pintype "passive"))
      (node (ref "U3") (pin "31") (pinfunction "PA23_31") (pintype "bidirectional"))
    )
    (net (code "50") (name "Net-(U3-PB08)") (class "Default")
      (node (ref "C7") (pin "1") (pinfunction "1_1") (pintype "passive"))
      (node (ref "U3") (pin "98") (pinfunction "PB08_98") (pintype "bidirectional"))
      (node (ref "Y1") (pin "1") (pinfunction "1_1") (pintype "passive"))
    )
    (net (code "51") (name "Net-(U3-PB09)") (class "Default")
      (node (ref "C9") (pin "1") (pinfunction "1_1") (pintype "passive"))
      (node (ref "U3") (pin "99") (pinfunction "PB09_99") (pintype "bidirectional"))
      (node (ref "Y1") (pin "3") (pinfunction "2_3") (pintype "passive"))
    )
    (net (code "52") (name "Net-(U3-VBG)") (class "Default")
      (node (ref "C20") (pin "1") (pinfunction "1_1") (pintype "passive"))
      (node (ref "R17") (pin "2") (pinfunction "2_2") (pintype "passive"))
      (node (ref "U3") (pin "97") (pinfunction "VBG_97") (pintype "bidirectional"))
    )
    (net (code "53") (name "Net-(U3-VDDOUT)") (class "Default")
      (node (ref "C17") (pin "1") (pinfunction "1_1") (pintype "passive"))
      (node (ref "C18") (pin "1") (pinfunction "1_1") (pintype "passive"))
      (node (ref "C21") (pin "1") (pinfunction "1_1") (pintype "passive"))
      (node (ref "C22") (pin "1") (pinfunction "1_1") (pintype "passive"))
      (node (ref "C24") (pin "1") (pinfunction "1_1") (pintype "passive"))
      (node (ref "C25") (pin "1") (pinfunction "1_1") (pintype "passive"))
      (node (ref "FB1") (pin "2") (pinfunction "2_2") (pintype "passive"))
      (node (ref "FB2") (pin "2") (pinfunction "2_2") (pintype "passive"))
      (node (ref "U3") (pin "18") (pinfunction "VDDCORE_18") (pintype "bidirectional"))
      (node (ref "U3") (pin "22") (pinfunction "VDDCORE_22") (pintype "bidirectional"))
      (node (ref "U3") (pin "39") (pinfunction "VDDCORE_39") (pintype "bidirectional"))
      (node (ref "U3") (pin "4") (pinfunction "VDDOUT_4") (pintype "bidirectional"))
      (node (ref "U3") (pin "76") (pinfunction "VDDCORE_76") (pintype "bidirectional"))
    )
    (net (code "54") (name "Net-(U3-VDDPLL)") (class "Default")
      (node (ref "C23") (pin "1") (pinfunction "1_1") (pintype "passive"))
      (node (ref "FB2") (pin "1") (pinfunction "1_1") (pintype "passive"))
      (node (ref "U3") (pin "86") (pinfunction "VDDPLL_86") (pintype "bidirectional"))
    )
    (net (code "55") (name "Net-(U3-VDDPLLUSB)") (class "Default")
      (node (ref "C14") (pin "1") (pinfunction "1_1") (pintype "passive"))
      (node (ref "L1") (pin "2") (pinfunction "2_2") (pintype "passive"))
      (node (ref "U3") (pin "90") (pinfunction "VDDPLLUSB_90") (pintype "bidirectional"))
    )
    (net (code "56") (name "Net-(U3-VDDUTMIC)") (class "Default")
      (node (ref "C19") (pin "1") (pinfunction "1_1") (pintype "passive"))
      (node (ref "FB1") (pin "1") (pinfunction "1_1") (pintype "passive"))
      (node (ref "U3") (pin "96") (pinfunction "VDDUTMIC_96") (pintype "bidirectional"))
    )
    (net (code "57") (name "Net-(U3-VREFP)") (class "Default")
      (node (ref "C26") (pin "1") (pinfunction "1_1") (pintype "passive"))
      (node (ref "FB3") (pin "2") (pinfunction "2_2") (pintype "passive"))
      (node (ref "U3") (pin "9") (pinfunction "VREFP_9") (pintype "bidirectional"))
    )
    (net (code "58") (name "Net-(U4-BICK)") (class "Default")
      (node (ref "R26") (pin "2") (pinfunction "2_2") (pintype "passive"))
      (node (ref "U4") (pin "48") (pinfunction "BICK_48") (pintype "bidirectional"))
    )
    (net (code "59") (name "Net-(U4-IN1{slash}IN1P)") (class "Default")
      (node (ref "C29") (pin "2") (pinfunction "2_2") (pintype "passive"))
      (node (ref "U4") (pin "10") (pinfunction "IN1/IN1P_10") (pintype "bidirectional"))
    )
    (net (code "60") (name "Net-(U4-IN2{slash}IN2P)") (class "Default")
      (node (ref "C30") (pin "2") (pinfunction "2_2") (pintype "passive"))
      (node (ref "U4") (pin "12") (pinfunction "IN2/IN2P_12") (pintype "bidirectional"))
    )
    (net (code "61") (name "Net-(U4-LOUT1)") (class "Default")
      (node (ref "C40") (pin "1") (pinfunction "1_1") (pintype "passive"))
      (node (ref "U4") (pin "36") (pinfunction "LOUT1_36") (pintype "bidirectional"))
    )
    (net (code "62") (name "Net-(U4-LOUT2)") (class "Default")
      (node (ref "C45") (pin "1") (pinfunction "1_1") (pintype "passive"))
      (node (ref "U4") (pin "34") (pinfunction "LOUT2_34") (pintype "bidirectional"))
    )
    (net (code "63") (name "Net-(U4-LOUT3)") (class "Default")
      (node (ref "C44") (pin "1") (pinfunction "1_1") (pintype "passive"))
      (node (ref "U4") (pin "32") (pinfunction "LOUT3_32") (pintype "bidirectional"))
    )
    (net (code "64") (name "Net-(U4-LOUT4)") (class "Default")
      (node (ref "C39") (pin "1") (pinfunction "1_1") (pintype "passive"))
      (node (ref "U4") (pin "30") (pinfunction "LOUT4_30") (pintype "bidirectional"))
    )
    (net (code "65") (name "Net-(U4-LRCLK)") (class "Default")
      (node (ref "R27") (pin "2") (pinfunction "2_2") (pintype "passive"))
      (node (ref "U4") (pin "1") (pinfunction "LRCLK_1") (pintype "bidirectional"))
    )
    (net (code "66") (name "Net-(U4-MCLK)") (class "Default")
      (node (ref "R25") (pin "2") (pinfunction "2_2") (pintype "passive"))
      (node (ref "U4") (pin "47") (pinfunction "MCLK_47") (pintype "bidirectional"))
    )
    (net (code "67") (name "Net-(U4-REGO)") (class "Default")
      (node (ref "C33") (pin "1") (pinfunction "1_1") (pintype "passive"))
      (node (ref "U4") (pin "41") (pinfunction "REGO_41") (pintype "bidirectional"))
    )
    (net (code "68") (name "Net-(U4-ROUT1)") (class "Default")
      (node (ref "C43") (pin "1") (pinfunction "1_1") (pintype "passive"))
      (node (ref "U4") (pin "35") (pinfunction "ROUT1_35") (pintype "bidirectional"))
    )
    (net (code "69") (name "Net-(U4-ROUT2)") (class "Default")
      (node (ref "C41") (pin "1") (pinfunction "1_1") (pintype "passive"))
      (node (ref "U4") (pin "33") (pinfunction "ROUT2_33") (pintype "bidirectional"))
    )
    (net (code "70") (name "Net-(U4-ROUT3)") (class "Default")
      (node (ref "C46") (pin "1") (pinfunction "1_1") (pintype "passive"))
      (node (ref "U4") (pin "31") (pinfunction "ROUT3_31") (pintype "bidirectional"))
    )
    (net (code "71") (name "Net-(U4-ROUT4)") (class "Default")
      (node (ref "C42") (pin "1") (pinfunction "1_1") (pintype "passive"))
      (node (ref "U4") (pin "29") (pinfunction "ROUT4_29") (pintype "bidirectional"))
    )
    (net (code "72") (name "Net-(U4-STDI1)") (class "Default")
      (node (ref "R28") (pin "2") (pinfunction "2_2") (pintype "passive"))
      (node (ref "U4") (pin "7") (pinfunction "STDI1_7") (pintype "bidirectional"))
    )
    (net (code "73") (name "Net-(U4-STDO1)") (class "Default")
      (node (ref "R24") (pin "2") (pinfunction "2_2") (pintype "passive"))
      (node (ref "U4") (pin "42") (pinfunction "STDO1_42") (pintype "bidirectional"))
    )
    (net (code "74") (name "Net-(U4-VCOM)") (class "Default")
      (node (ref "C34") (pin "1") (pinfunction "1_1") (pintype "passive"))
      (node (ref "U4") (pin "20") (pinfunction "VCOM_20") (pintype "bidirectional"))
    )
    (net (code "75") (name "Net-(U5-Y)") (class "Default")
      (node (ref "R46") (pin "1") (pinfunction "1_1") (pintype "passive"))
      (node (ref "U5") (pin "4") (pinfunction "Y_4") (pintype "bidirectional"))
    )
    (net (code "76") (name "Net-(U6-A)") (class "Default")
      (node (ref "D3") (pin "C") (pinfunction "C_C") (pintype "passive"))
      (node (ref "R45") (pin "2") (pinfunction "2_2") (pintype "passive"))
      (node (ref "U6") (pin "2") (pinfunction "A_2") (pintype "bidirectional"))
    )
    (net (code "77") (name "RXD") (class "Default")
      (node (ref "J9") (pin "P$3") (pinfunction "RXI_P$3") (pintype "bidirectional"))
      (node (ref "U3") (pin "51") (pinfunction "PD28_51") (pintype "bidirectional"))
    )
    (net (code "78") (name "SDCD") (class "Default")
      (node (ref "J12") (pin "CD1") (pinfunction "CD1_CD1") (pintype "bidirectional"))
      (node (ref "J12") (pin "CD2") (pinfunction "CD2_CD2") (pintype "bidirectional"))
      (node (ref "R18") (pin "1") (pinfunction "1_1") (pintype "passive"))
      (node (ref "U3") (pin "49") (pinfunction "PD18_49") (pintype "bidirectional"))
    )
    (net (code "79") (name "SDCLK") (class "Default")
      (node (ref "J12") (pin "CLK") (pinfunction "CLK_CLK") (pintype "bidirectional"))
      (node (ref "U3") (pin "40") (pinfunction "PA25_40") (pintype "bidirectional"))
    )
    (net (code "80") (name "SDCMD") (class "Default")
      (node (ref "J12") (pin "CMD") (pinfunction "CMD_CMD") (pintype "bidirectional"))
      (node (ref "R23") (pin "1") (pinfunction "1_1") (pintype "passive"))
      (node (ref "U3") (pin "79") (pinfunction "PA28_79") (pintype "bidirectional"))
    )
    (net (code "81") (name "SDD0") (class "Default")
      (node (ref "J12") (pin "DAT0") (pinfunction "DAT0_DAT0") (pintype "bidirectional"))
      (node (ref "R21") (pin "1") (pinfunction "1_1") (pintype "passive"))
      (node (ref "U3") (pin "82") (pinfunction "PA30_82") (pintype "bidirectional"))
    )
    (net (code "82") (name "SDD1") (class "Default")
      (node (ref "J12") (pin "DAT1") (pinfunction "DAT1_DAT1") (pintype "bidirectional"))
      (node (ref "R22") (pin "1") (pinfunction "1_1") (pintype "passive"))
      (node (ref "U3") (pin "83") (pinfunction "PA31_83") (pintype "bidirectional"))
    )
    (net (code "83") (name "SDD2") (class "Default")
      (node (ref "J12") (pin "DAT2") (pinfunction "DAT2_DAT2") (pintype "bidirectional"))
      (node (ref "R19") (pin "1") (pinfunction "1_1") (pintype "passive"))
      (node (ref "U3") (pin "42") (pinfunction "PA26_42") (pintype "bidirectional"))
    )
    (net (code "84") (name "SDD3") (class "Default")
      (node (ref "J12") (pin "CD/DAT3") (pinfunction "CD/DAT3_CD/DAT3") (pintype "bidirectional"))
      (node (ref "R20") (pin "1") (pinfunction "1_1") (pintype "passive"))
      (node (ref "U3") (pin "50") (pinfunction "PA27_50") (pintype "bidirectional"))
    )
    (net (code "85") (name "SHIELD") (class "Default")
      (node (ref "J4") (pin "SHIELD1") (pinfunction "SHIELD_SHIELD1") (pintype "bidirectional"))
      (node (ref "J4") (pin "SHIELD2") (pinfunction "SHIELD_SHIELD2") (pintype "bidirectional"))
      (node (ref "J4") (pin "SHIELD3") (pinfunction "SHIELD_SHIELD3") (pintype "bidirectional"))
    )
    (net (code "86") (name "SWCLK{slash}TCK") (class "Default")
      (node (ref "J5") (pin "4") (pinfunction "SWDCLK/TCK_4") (pintype "bidirectional"))
      (node (ref "R9") (pin "1") (pinfunction "1_1") (pintype "passive"))
      (node (ref "TP6") (pin "P$1") (pinfunction "1_P$1") (pintype "bidirectional"))
      (node (ref "U3") (pin "63") (pinfunction "PB07_63") (pintype "bidirectional"))
    )
    (net (code "87") (name "SWDIO{slash}TMS") (class "Default")
      (node (ref "J5") (pin "2") (pinfunction "SWDIO/TMS_2") (pintype "bidirectional"))
      (node (ref "R6") (pin "1") (pinfunction "1_1") (pintype "passive"))
      (node (ref "TP5") (pin "P$1") (pinfunction "1_P$1") (pintype "bidirectional"))
      (node (ref "U3") (pin "57") (pinfunction "PB06_57") (pintype "bidirectional"))
    )
    (net (code "88") (name "TDI") (class "Default")
      (node (ref "J5") (pin "8") (pinfunction "NC/TDI_8") (pintype "bidirectional"))
      (node (ref "TP8") (pin "P$1") (pinfunction "1_P$1") (pintype "bidirectional"))
      (node (ref "U3") (pin "74") (pinfunction "PB04_74") (pintype "bidirectional"))
    )
    (net (code "89") (name "TDMI") (class "Default")
      (node (ref "R24") (pin "1") (pinfunction "1_1") (pintype "passive"))
      (node (ref "U3") (pin "46") (pinfunction "PA10_46") (pintype "bidirectional"))
    )
    (net (code "90") (name "TDMO") (class "Default")
      (node (ref "R28") (pin "1") (pinfunction "1_1") (pintype "passive"))
      (node (ref "U3") (pin "36") (pinfunction "PD26_36") (pintype "bidirectional"))
    )
    (net (code "91") (name "TDO") (class "Default")
      (node (ref "J5") (pin "6") (pinfunction "SWO/TDO_6") (pintype "bidirectional"))
      (node (ref "TP7") (pin "P$1") (pinfunction "1_P$1") (pintype "bidirectional"))
      (node (ref "U3") (pin "77") (pinfunction "PB05_77") (pintype "bidirectional"))
    )
    (net (code "92") (name "TXD") (class "Default")
      (node (ref "J9") (pin "P$2") (pinfunction "TXO_P$2") (pintype "bidirectional"))
      (node (ref "U3") (pin "23") (pinfunction "PD30_23") (pintype "bidirectional"))
    )
    (net (code "93") (name "UIA1") (class "Default")
      (node (ref "J10") (pin "7") (pinfunction "7_7") (pintype "passive"))
      (node (ref "U3") (pin "17") (pinfunction "PB02_17") (pintype "bidirectional"))
    )
    (net (code "94") (name "UIA2") (class "Default")
      (node (ref "J10") (pin "5") (pinfunction "5_5") (pintype "passive"))
      (node (ref "U3") (pin "20") (pinfunction "PB03_20") (pintype "bidirectional"))
    )
    (net (code "95") (name "UIA3") (class "Default")
      (node (ref "J10") (pin "3") (pinfunction "3_3") (pintype "passive"))
      (node (ref "U3") (pin "21") (pinfunction "PA21_21") (pintype "bidirectional"))
    )
    (net (code "96") (name "UIA4") (class "Default")
      (node (ref "J10") (pin "1") (pinfunction "1_1") (pintype "passive"))
      (node (ref "U3") (pin "16") (pinfunction "PA17_16") (pintype "bidirectional"))
    )
    (net (code "97") (name "UID1") (class "Default")
      (node (ref "J11") (pin "15") (pinfunction "15_15") (pintype "passive"))
      (node (ref "U3") (pin "65") (pinfunction "PD12_65") (pintype "bidirectional"))
    )
    (net (code "98") (name "UID2") (class "Default")
      (node (ref "J11") (pin "13") (pinfunction "13_13") (pintype "passive"))
      (node (ref "U3") (pin "69") (pinfunction "PD11_69") (pintype "bidirectional"))
    )
    (net (code "99") (name "UID3") (class "Default")
      (node (ref "J11") (pin "11") (pinfunction "11_11") (pintype "passive"))
      (node (ref "U3") (pin "78") (pinfunction "PD09_78") (pintype "bidirectional"))
    )
    (net (code "100") (name "UID4") (class "Default")
      (node (ref "J11") (pin "9") (pinfunction "9_9") (pintype "passive"))
      (node (ref "U3") (pin "80") (pinfunction "PD08_80") (pintype "bidirectional"))
    )
    (net (code "101") (name "UID5") (class "Default")
      (node (ref "J11") (pin "7") (pinfunction "7_7") (pintype "passive"))
      (node (ref "U3") (pin "84") (pinfunction "PD07_84") (pintype "bidirectional"))
    )
    (net (code "102") (name "UID6") (class "Default")
      (node (ref "J11") (pin "5") (pinfunction "5_5") (pintype "passive"))
      (node (ref "U3") (pin "85") (pinfunction "PD06_85") (pintype "bidirectional"))
    )
    (net (code "103") (name "UID7") (class "Default")
      (node (ref "J11") (pin "3") (pinfunction "3_3") (pintype "passive"))
      (node (ref "U3") (pin "87") (pinfunction "PD05_87") (pintype "bidirectional"))
    )
    (net (code "104") (name "UID8") (class "Default")
      (node (ref "J11") (pin "1") (pinfunction "1_1") (pintype "passive"))
      (node (ref "U3") (pin "88") (pinfunction "PD04_88") (pintype "bidirectional"))
    )
    (net (code "105") (name "UID9") (class "Default")
      (node (ref "J10") (pin "15") (pinfunction "15_15") (pintype "passive"))
      (node (ref "U3") (pin "89") (pinfunction "PD03_89") (pintype "bidirectional"))
    )
    (net (code "106") (name "UID10") (class "Default")
      (node (ref "J10") (pin "13") (pinfunction "13_13") (pintype "passive"))
      (node (ref "U3") (pin "91") (pinfunction "PD02_91") (pintype "bidirectional"))
    )
    (net (code "107") (name "UID11") (class "Default")
      (node (ref "J10") (pin "11") (pinfunction "11_11") (pintype "passive"))
      (node (ref "U3") (pin "92") (pinfunction "PD01_92") (pintype "bidirectional"))
    )
    (net (code "108") (name "UID12") (class "Default")
      (node (ref "J10") (pin "9") (pinfunction "9_9") (pintype "passive"))
      (node (ref "U3") (pin "1") (pinfunction "PD00_1") (pintype "bidirectional"))
    )
    (net (code "109") (name "USERSW") (class "Default")
      (node (ref "S3") (pin "3") (pinfunction "2_3") (pintype "passive"))
      (node (ref "S4") (pin "2") (pinfunction "2_2") (pintype "passive"))
      (node (ref "U3") (pin "26") (pinfunction "PA22_26") (pintype "bidirectional"))
    )
    (net (code "110") (name "VBDET") (class "Default")
      (node (ref "R4") (pin "1") (pinfunction "1_1") (pintype "passive"))
      (node (ref "R5") (pin "2") (pinfunction "2_2") (pintype "passive"))
      (node (ref "U3") (pin "47") (pinfunction "PD19_47") (pintype "bidirectional"))
    )
    (net (code "111") (name "VBUS") (class "Default")
      (node (ref "C2") (pin "1") (pinfunction "1_1") (pintype "passive"))
      (node (ref "D1") (pin "A") (pinfunction "A_A") (pintype "passive"))
      (node (ref "J4") (pin "VBUS") (pinfunction "VBUS_VBUS") (pintype "bidirectional"))
      (node (ref "R4") (pin "2") (pinfunction "2_2") (pintype "passive"))
    )
    (net (code "112") (name "VCCA") (class "Default")
      (node (ref "C31") (pin "1") (pinfunction "1_1") (pintype "passive"))
      (node (ref "C32") (pin "1") (pinfunction "1_1") (pintype "passive"))
      (node (ref "C37") (pin "1") (pinfunction "1_1") (pintype "passive"))
      (node (ref "C38") (pin "1") (pinfunction "1_1") (pintype "passive"))
      (node (ref "C5") (pin "1") (pinfunction "1_1") (pintype "passive"))
      (node (ref "J6") (pin "1") (pinfunction "1_1") (pintype "passive"))
      (node (ref "JP1") (pin "1") (pinfunction "1_1") (pintype "passive"))
      (node (ref "JP1") (pin "2") (pinfunction "2_2") (pintype "passive"))
      (node (ref "R11") (pin "2") (pinfunction "2_2") (pintype "passive"))
      (node (ref "U1") (pin "2") (pinfunction "OUT_2") (pintype "output"))
      (node (ref "U1") (pin "4") (pinfunction "OUT_4") (pintype "output"))
      (node (ref "U4") (pin "18") (pinfunction "AVDD1_18") (pintype "bidirectional"))
      (node (ref "U4") (pin "37") (pinfunction "AVDD2_37") (pintype "bidirectional"))
    )
    (net (code "113") (name "VIN") (class "Default")
      (node (ref "J1") (pin "1") (pinfunction "1_1") (pintype "passive"))
      (node (ref "J1") (pin "2") (pinfunction "2_2") (pintype "passive"))
      (node (ref "Q1") (pin "3") (pinfunction "D_3") (pintype "passive"))
    )
    (net (code "114") (name "unconnected-(J4-USBID-PadID)") (class "Default")
      (node (ref "J4") (pin "ID") (pinfunction "USBID_ID") (pintype "bidirectional"))
    )
    (net (code "115") (name "unconnected-(J5-KEY-Pad7)") (class "Default")
      (node (ref "J5") (pin "7") (pinfunction "KEY_7") (pintype "bidirectional"))
    )
    (net (code "116") (name "unconnected-(J9-CTS-PadP$5)") (class "Default")
      (node (ref "J9") (pin "P$5") (pinfunction "CTS_P$5") (pintype "bidirectional"))
    )
    (net (code "117") (name "unconnected-(J9-DTR-PadP$1)") (class "Default")
      (node (ref "J9") (pin "P$1") (pinfunction "DTR_P$1") (pintype "bidirectional"))
    )
    (net (code "118") (name "unconnected-(J9-VCC-PadP$4)") (class "Default")
      (node (ref "J9") (pin "P$4") (pinfunction "VCC_P$4") (pintype "bidirectional"))
    )
    (net (code "119") (name "unconnected-(U3-JTAGSEL-Pad73)") (class "Default")
      (node (ref "U3") (pin "73") (pinfunction "JTAGSEL_73") (pintype "bidirectional"))
    )
    (net (code "120") (name "unconnected-(U3-PA02-Pad66)") (class "Default")
      (node (ref "U3") (pin "66") (pinfunction "PA02_66") (pintype "bidirectional"))
    )
    (net (code "121") (name "unconnected-(U3-PA05-Pad52)") (class "Default")
      (node (ref "U3") (pin "52") (pinfunction "PA05_52") (pintype "bidirectional"))
    )
    (net (code "122") (name "unconnected-(U3-PA07-Pad24)") (class "Default")
      (node (ref "U3") (pin "24") (pinfunction "PA07_24") (pintype "bidirectional"))
    )
    (net (code "123") (name "unconnected-(U3-PA08-Pad25)") (class "Default")
      (node (ref "U3") (pin "25") (pinfunction "PA08_25") (pintype "bidirectional"))
    )
    (net (code "124") (name "unconnected-(U3-PA09-Pad54)") (class "Default")
      (node (ref "U3") (pin "54") (pinfunction "PA09_54") (pintype "bidirectional"))
    )
    (net (code "125") (name "unconnected-(U3-PA11-Pad44)") (class "Default")
      (node (ref "U3") (pin "44") (pinfunction "PA11_44") (pintype "bidirectional"))
    )
    (net (code "126") (name "unconnected-(U3-PA12-Pad48)") (class "Default")
      (node (ref "U3") (pin "48") (pinfunction "PA12_48") (pintype "bidirectional"))
    )
    (net (code "127") (name "unconnected-(U3-PA13-Pad27)") (class "Default")
      (node (ref "U3") (pin "27") (pinfunction "PA13_27") (pintype "bidirectional"))
    )
    (net (code "128") (name "unconnected-(U3-PA14-Pad34)") (class "Default")
      (node (ref "U3") (pin "34") (pinfunction "PA14_34") (pintype "bidirectional"))
    )
    (net (code "129") (name "unconnected-(U3-PA15-Pad33)") (class "Default")
      (node (ref "U3") (pin "33") (pinfunction "PA15_33") (pintype "bidirectional"))
    )
    (net (code "130") (name "unconnected-(U3-PA19-Pad14)") (class "Default")
      (node (ref "U3") (pin "14") (pinfunction "PA19_14") (pintype "bidirectional"))
    )
    (net (code "131") (name "unconnected-(U3-PA20-Pad13)") (class "Default")
      (node (ref "U3") (pin "13") (pinfunction "PA20_13") (pintype "bidirectional"))
    )
    (net (code "132") (name "unconnected-(U3-PA24-Pad38)") (class "Default")
      (node (ref "U3") (pin "38") (pinfunction "PA24_38") (pintype "bidirectional"))
    )
    (net (code "133") (name "unconnected-(U3-PB12-Pad61)") (class "Default")
      (node (ref "U3") (pin "61") (pinfunction "PB12_61") (pintype "bidirectional"))
    )
    (net (code "134") (name "unconnected-(U3-PB13-Pad100)") (class "Default")
      (node (ref "U3") (pin "100") (pinfunction "PB13_100") (pintype "bidirectional"))
    )
    (net (code "135") (name "unconnected-(U3-PD10-Pad71)") (class "Default")
      (node (ref "U3") (pin "71") (pinfunction "PD10_71") (pintype "bidirectional"))
    )
    (net (code "136") (name "unconnected-(U3-PD13-Pad62)") (class "Default")
      (node (ref "U3") (pin "62") (pinfunction "PD13_62") (pintype "bidirectional"))
    )
    (net (code "137") (name "unconnected-(U3-PD14-Pad59)") (class "Default")
      (node (ref "U3") (pin "59") (pinfunction "PD14_59") (pintype "bidirectional"))
    )
    (net (code "138") (name "unconnected-(U3-PD17-Pad53)") (class "Default")
      (node (ref "U3") (pin "53") (pinfunction "PD17_53") (pintype "bidirectional"))
    )
    (net (code "139") (name "unconnected-(U3-PD20-Pad45)") (class "Default")
      (node (ref "U3") (pin "45") (pinfunction "PD20_45") (pintype "bidirectional"))
    )
    (net (code "140") (name "unconnected-(U3-PD21-Pad43)") (class "Default")
      (node (ref "U3") (pin "43") (pinfunction "PD21_43") (pintype "bidirectional"))
    )
    (net (code "141") (name "unconnected-(U3-PD22-Pad41)") (class "Default")
      (node (ref "U3") (pin "41") (pinfunction "PD22_41") (pintype "bidirectional"))
    )
    (net (code "142") (name "unconnected-(U3-PD24-Pad37)") (class "Default")
      (node (ref "U3") (pin "37") (pinfunction "PD24_37") (pintype "bidirectional"))
    )
    (net (code "143") (name "unconnected-(U3-PD25-Pad35)") (class "Default")
      (node (ref "U3") (pin "35") (pinfunction "PD25_35") (pintype "bidirectional"))
    )
    (net (code "144") (name "unconnected-(U3-PD27-Pad32)") (class "Default")
      (node (ref "U3") (pin "32") (pinfunction "PD27_32") (pintype "bidirectional"))
    )
    (net (code "145") (name "unconnected-(U3-PD31-Pad2)") (class "Default")
      (node (ref "U3") (pin "2") (pinfunction "PD31_2") (pintype "bidirectional"))
    )
    (net (code "146") (name "unconnected-(U3-TST-Pad60)") (class "Default")
      (node (ref "U3") (pin "60") (pinfunction "TST_60") (pintype "bidirectional"))
    )
    (net (code "147") (name "unconnected-(U4-IN1N-Pad9)") (class "Default")
      (node (ref "U4") (pin "9") (pinfunction "IN1N_9") (pintype "bidirectional"))
    )
    (net (code "148") (name "unconnected-(U4-IN2N-Pad11)") (class "Default")
      (node (ref "U4") (pin "11") (pinfunction "IN2N_11") (pintype "bidirectional"))
    )
    (net (code "149") (name "unconnected-(U4-IN3{slash}IN3P-Pad14)") (class "Default")
      (node (ref "U4") (pin "14") (pinfunction "IN3/IN3P_14") (pintype "bidirectional"))
    )
    (net (code "150") (name "unconnected-(U4-IN4{slash}IN4P-Pad16)") (class "Default")
      (node (ref "U4") (pin "16") (pinfunction "IN4/IN4P_16") (pintype "bidirectional"))
    )
    (net (code "151") (name "unconnected-(U4-IN5N-Pad21)") (class "Default")
      (node (ref "U4") (pin "21") (pinfunction "IN5N_21") (pintype "bidirectional"))
    )
    (net (code "152") (name "unconnected-(U4-IN5{slash}IN5P-Pad22)") (class "Default")
      (node (ref "U4") (pin "22") (pinfunction "IN5/IN5P_22") (pintype "bidirectional"))
    )
    (net (code "153") (name "unconnected-(U4-IN6N-Pad23)") (class "Default")
      (node (ref "U4") (pin "23") (pinfunction "IN6N_23") (pintype "bidirectional"))
    )
    (net (code "154") (name "unconnected-(U4-IN6{slash}IN6P-Pad24)") (class "Default")
      (node (ref "U4") (pin "24") (pinfunction "IN6/IN6P_24") (pintype "bidirectional"))
    )
    (net (code "155") (name "unconnected-(U4-LOUT6-Pad26)") (class "Default")
      (node (ref "U4") (pin "26") (pinfunction "LOUT6_26") (pintype "bidirectional"))
    )
    (net (code "156") (name "unconnected-(U4-MICBIAS-Pad17)") (class "Default")
      (node (ref "U4") (pin "17") (pinfunction "MICBIAS_17") (pintype "bidirectional"))
    )
    (net (code "157") (name "unconnected-(U4-ROUT6-Pad25)") (class "Default")
      (node (ref "U4") (pin "25") (pinfunction "ROUT6_25") (pintype "bidirectional"))
    )
    (net (code "158") (name "unconnected-(U4-STDO2-Pad43)") (class "Default")
      (node (ref "U4") (pin "43") (pinfunction "STDO2_43") (pintype "bidirectional"))
    )
    (net (code "159") (name "unconnected-(U4-STDO3-Pad44)") (class "Default")
      (node (ref "U4") (pin "44") (pinfunction "STDO3_44") (pintype "bidirectional"))
    )
  )
)
